# driver_board.net
KiCad netlist of a schematic drawn in EAGLE
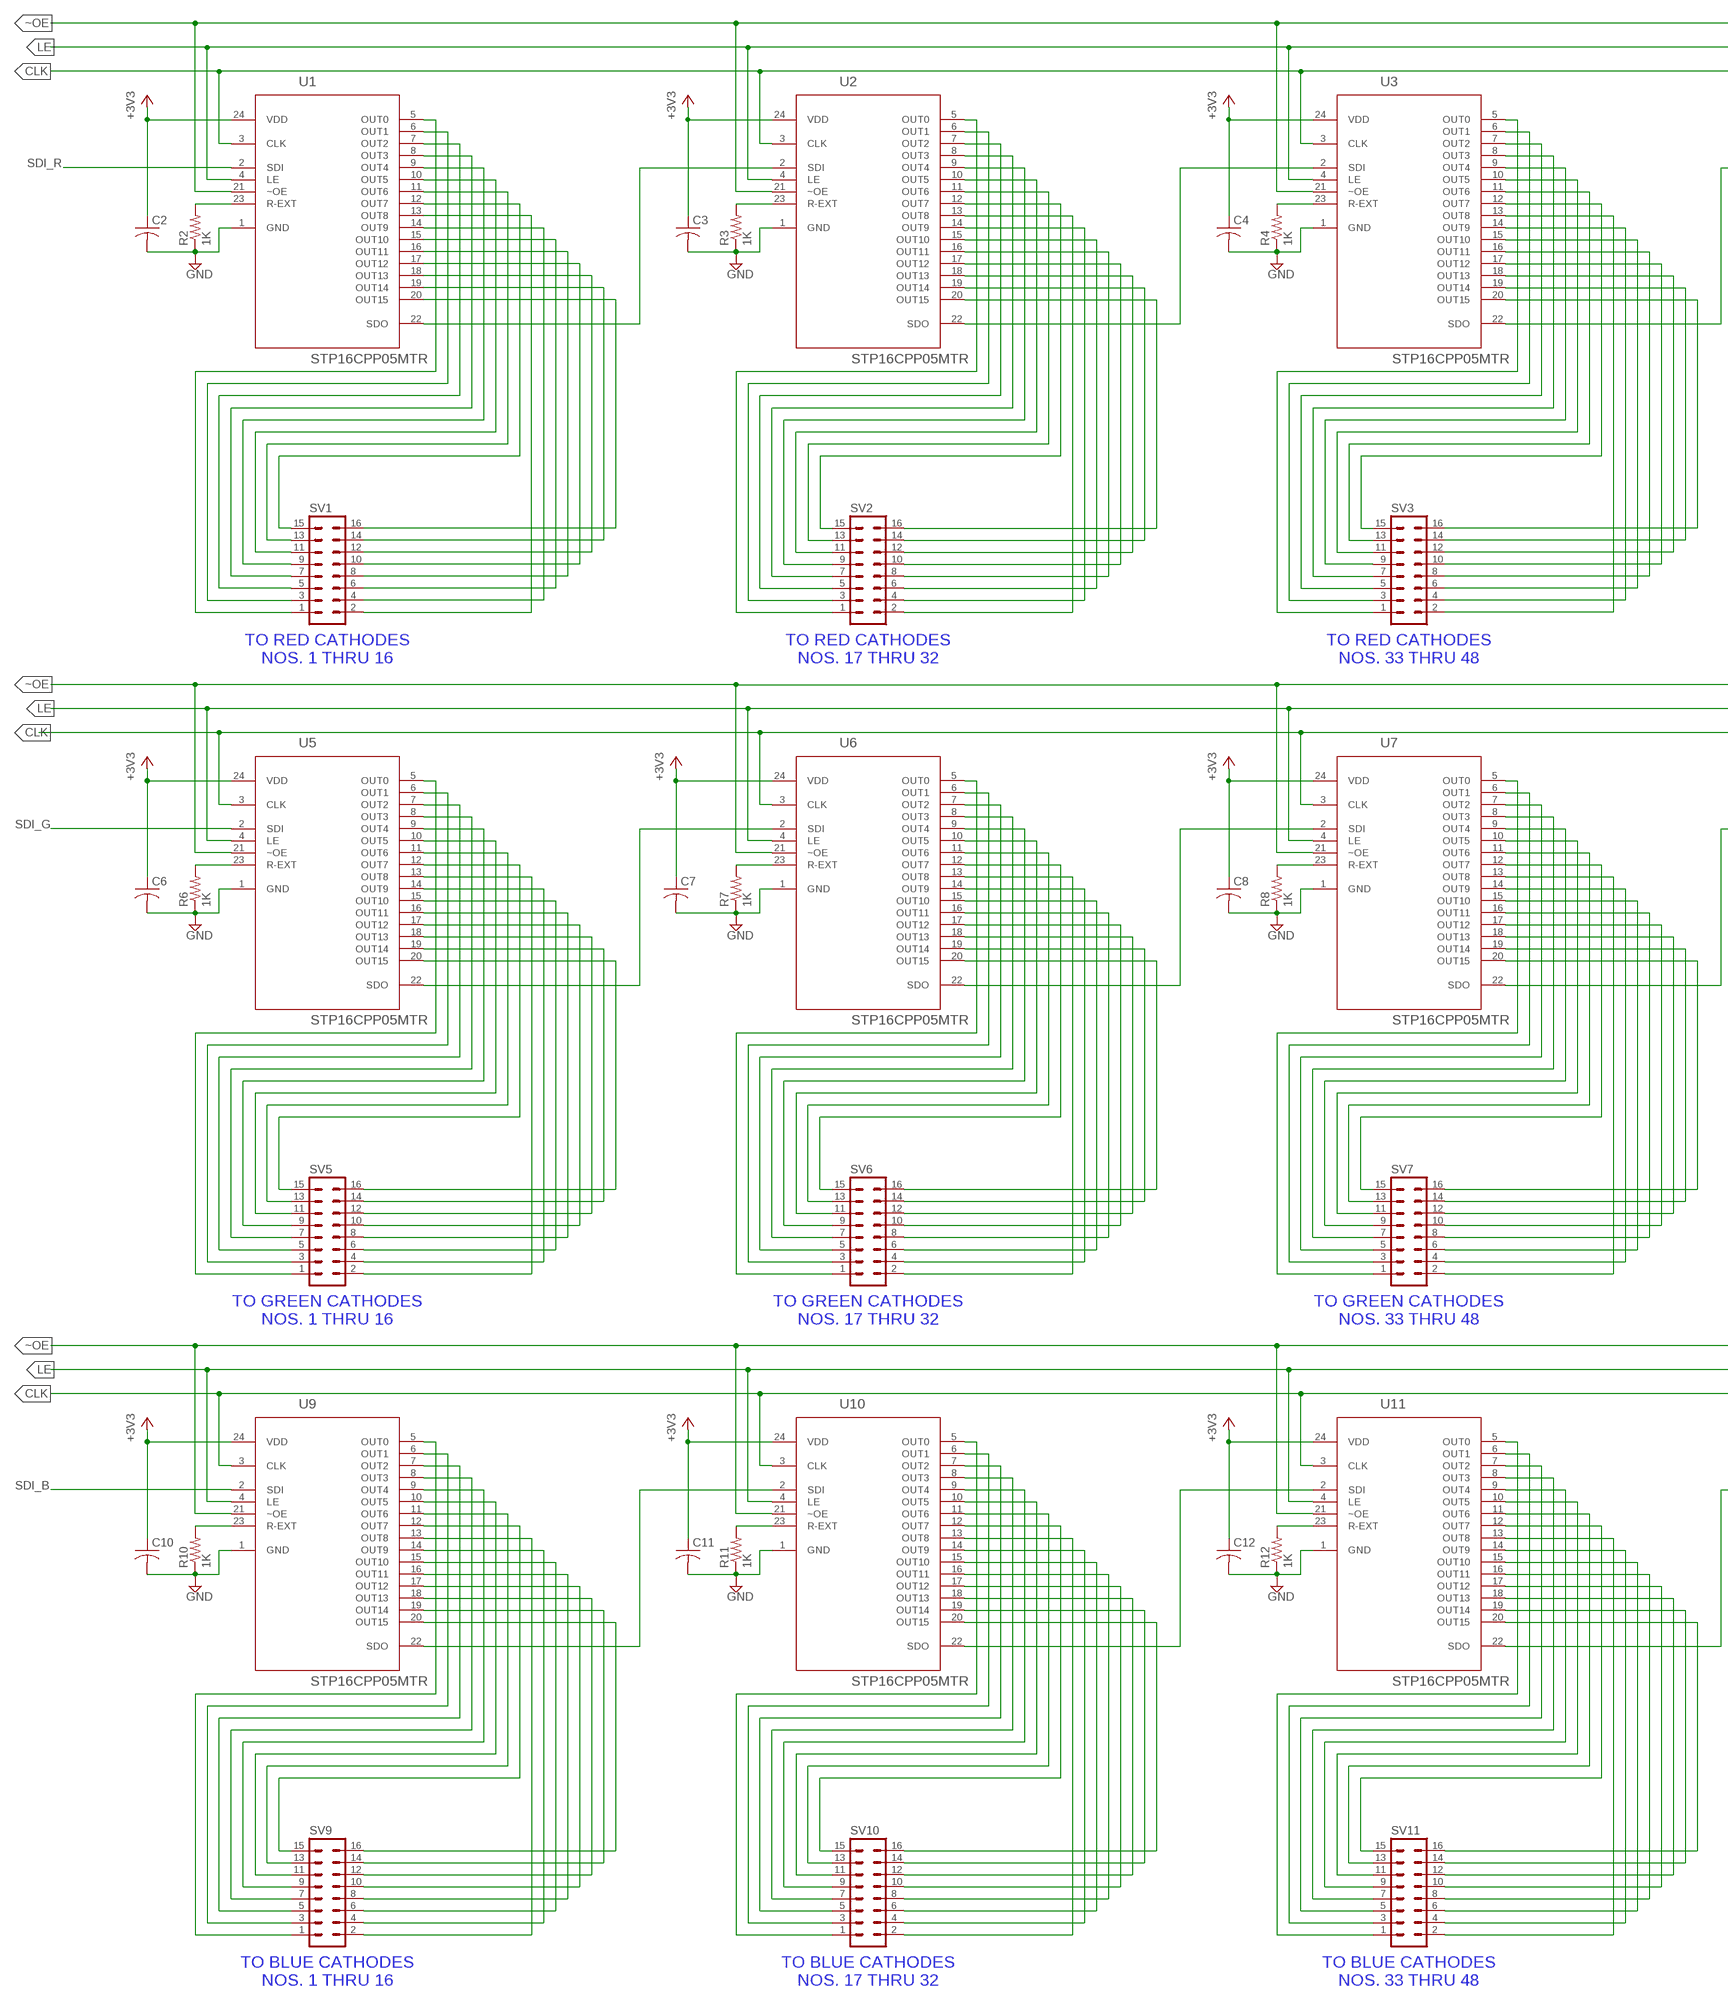
[diagram p0: schematic, sheet 1, part 1 of 2]
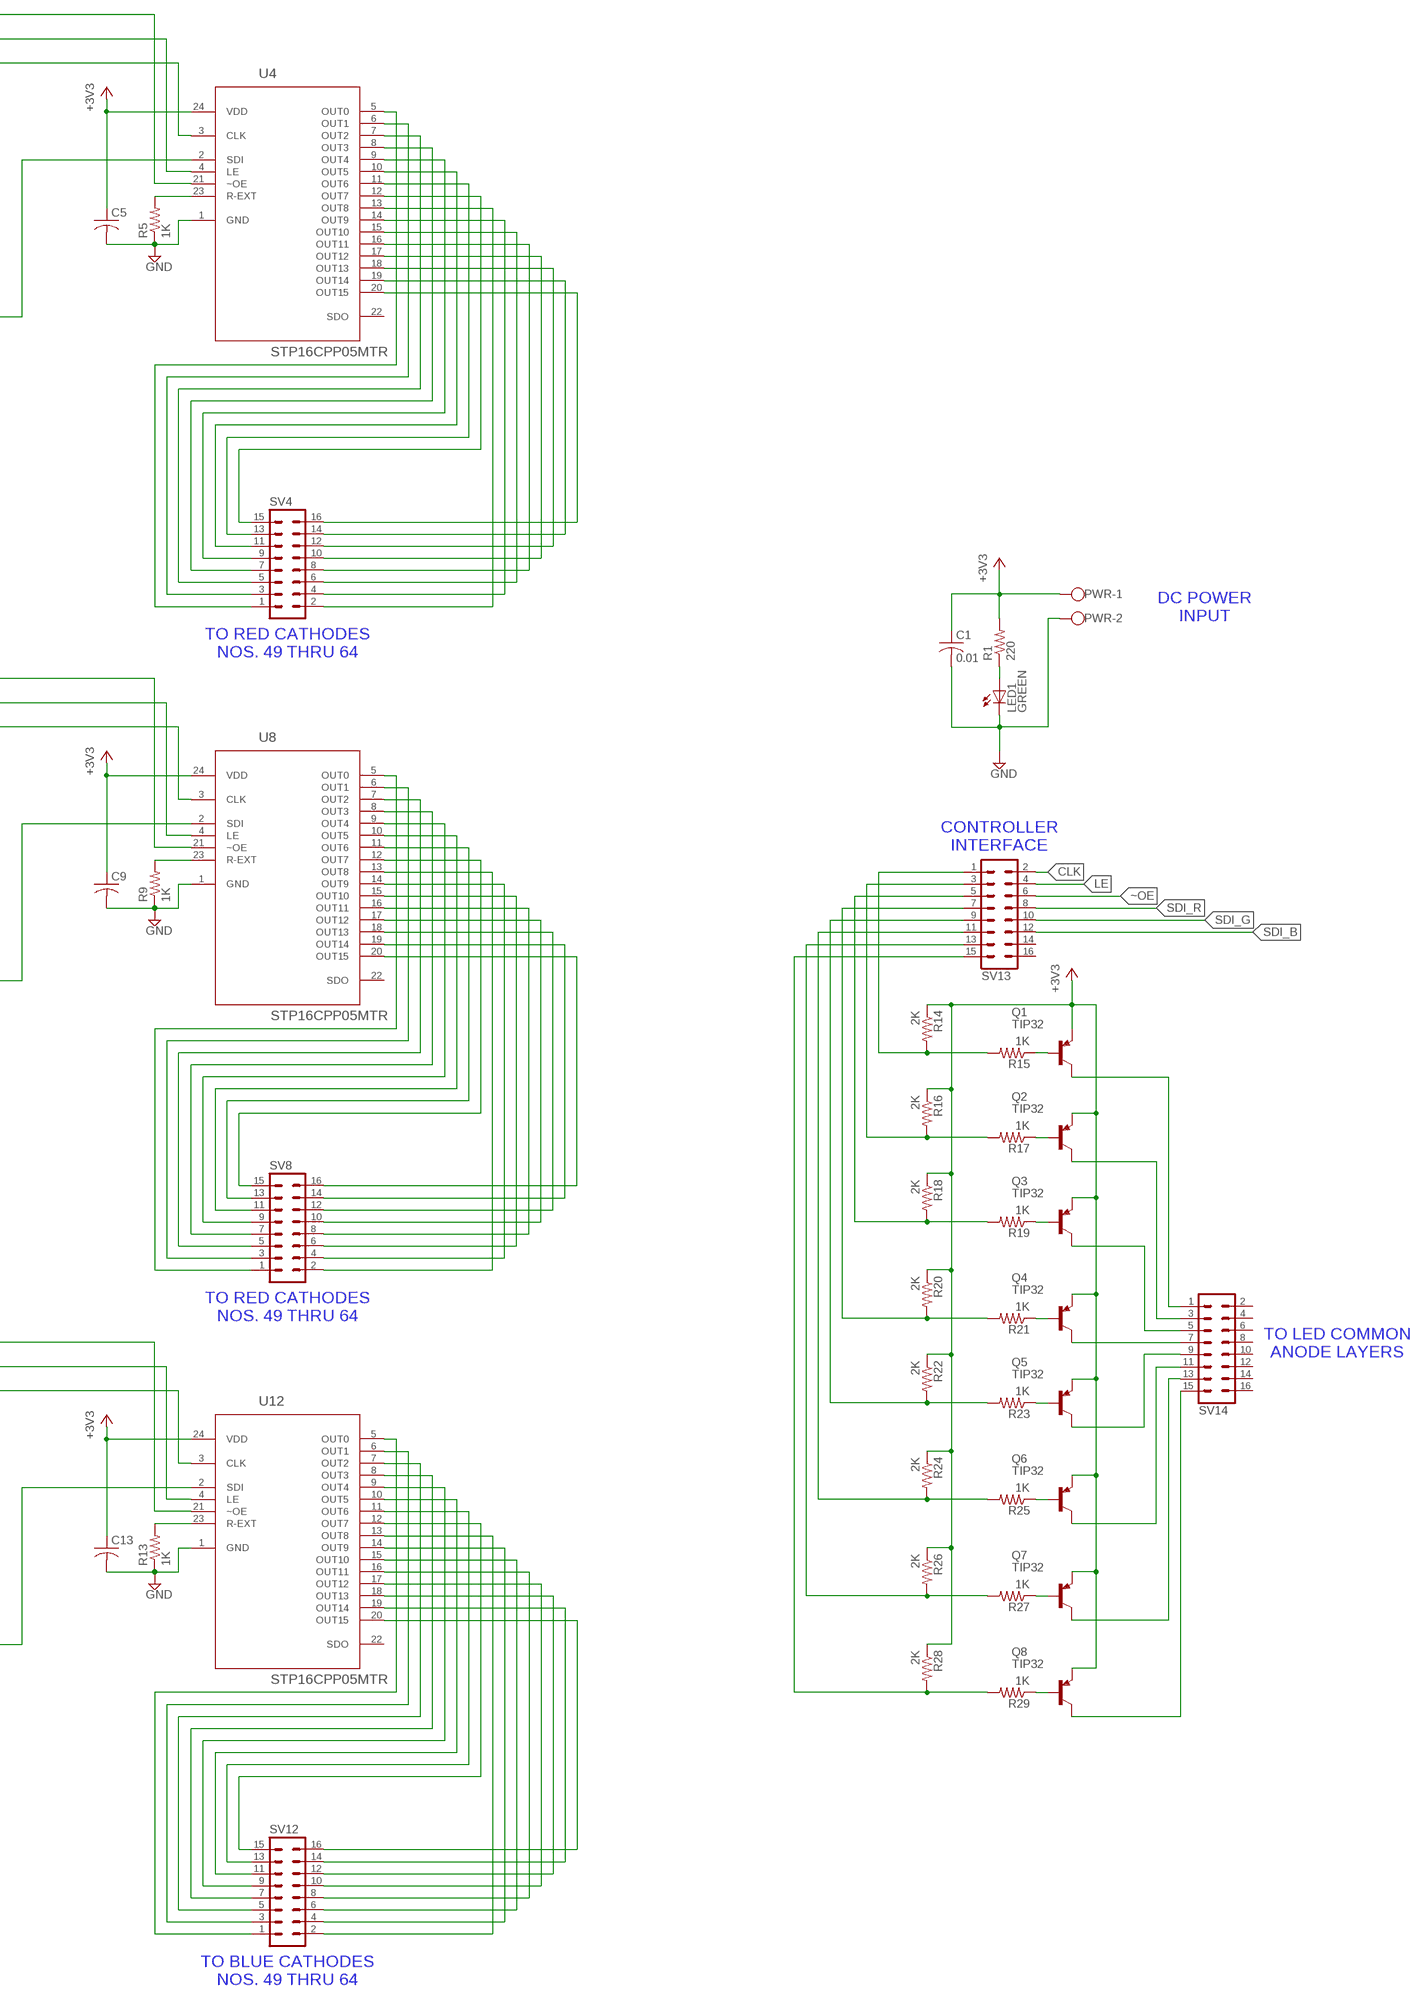
[diagram p1: schematic, sheet 1, part 2 of 2]

(export (version "E")
  (design (tool "Eeschema 10.0.6"))
  (components
    (comp (ref "C1")
      (value "0.01")
      (footprint "eagle-import:C0805")
      (fields (field (name "MPN") "MCCA001261"))
      (libsource (lib "eagle-import") (part "C-USC0805"))
    )
    (comp (ref "C2")
      (value "C-USC0805")
      (footprint "eagle-import:C0805")
      (fields (field (name "MPN") "MCCA001261"))
      (libsource (lib "eagle-import") (part "C-USC0805"))
    )
    (comp (ref "C3")
      (value "C-USC0805")
      (footprint "eagle-import:C0805")
      (fields (field (name "MPN") "MCCA001261"))
      (libsource (lib "eagle-import") (part "C-USC0805"))
    )
    (comp (ref "C4")
      (value "C-USC0805")
      (footprint "eagle-import:C0805")
      (fields (field (name "MPN") "MCCA001261"))
      (libsource (lib "eagle-import") (part "C-USC0805"))
    )
    (comp (ref "C5")
      (value "C-USC0805")
      (footprint "eagle-import:C0805")
      (fields (field (name "MPN") "MCCA001261"))
      (libsource (lib "eagle-import") (part "C-USC0805"))
    )
    (comp (ref "C6")
      (value "C-USC0805")
      (footprint "eagle-import:C0805")
      (fields (field (name "MPN") "MCCA001261"))
      (libsource (lib "eagle-import") (part "C-USC0805"))
    )
    (comp (ref "C7")
      (value "C-USC0805")
      (footprint "eagle-import:C0805")
      (fields (field (name "MPN") "MCCA001261"))
      (libsource (lib "eagle-import") (part "C-USC0805"))
    )
    (comp (ref "C8")
      (value "C-USC0805")
      (footprint "eagle-import:C0805")
      (fields (field (name "MPN") "MCCA001261"))
      (libsource (lib "eagle-import") (part "C-USC0805"))
    )
    (comp (ref "C9")
      (value "C-USC0805")
      (footprint "eagle-import:C0805")
      (fields (field (name "MPN") "MCCA001261"))
      (libsource (lib "eagle-import") (part "C-USC0805"))
    )
    (comp (ref "C10")
      (value "C-USC0805")
      (footprint "eagle-import:C0805")
      (fields (field (name "MPN") "MCCA001261"))
      (libsource (lib "eagle-import") (part "C-USC0805"))
    )
    (comp (ref "C11")
      (value "C-USC0805")
      (footprint "eagle-import:C0805")
      (fields (field (name "MPN") "MCCA001261"))
      (libsource (lib "eagle-import") (part "C-USC0805"))
    )
    (comp (ref "C12")
      (value "C-USC0805")
      (footprint "eagle-import:C0805")
      (fields (field (name "MPN") "MCCA001261"))
      (libsource (lib "eagle-import") (part "C-USC0805"))
    )
    (comp (ref "C13")
      (value "C-USC0805")
      (footprint "eagle-import:C0805")
      (fields (field (name "MPN") "MCCA001261"))
      (libsource (lib "eagle-import") (part "C-USC0805"))
    )
    (comp (ref "LED1")
      (value "GREEN")
      (footprint "eagle-import:LED5MM")
      (fields (field (name "MF") "SLI (CML/IDI)") (field (name "MPN") "CMD17-21VGD/TR8"))
      (libsource (lib "eagle-import") (part "LED5MM"))
    )
    (comp (ref "PWR")
      (value "W237-102")
      (footprint "eagle-import:W237-102")
      (fields (field (name "MPN") "237-102") (field (name "OC_NEWARK") "unknown"))
      (libsource (lib "eagle-import") (part "W237-102"))
    )
    (comp (ref "Q1")
      (value "TIP32")
      (footprint "eagle-import:TO220AV")
      (fields (field (name "MF") "ON SEMICONDUCTOR") (field (name "MPN") "TIP32BG"))
      (libsource (lib "eagle-import") (part "TIP32"))
    )
    (comp (ref "Q2")
      (value "TIP32")
      (footprint "eagle-import:TO220AV")
      (fields (field (name "MF") "ON SEMICONDUCTOR") (field (name "MPN") "TIP32BG"))
      (libsource (lib "eagle-import") (part "TIP32"))
    )
    (comp (ref "Q3")
      (value "TIP32")
      (footprint "eagle-import:TO220AV")
      (fields (field (name "MF") "ON SEMICONDUCTOR") (field (name "MPN") "TIP32BG"))
      (libsource (lib "eagle-import") (part "TIP32"))
    )
    (comp (ref "Q4")
      (value "TIP32")
      (footprint "eagle-import:TO220AV")
      (fields (field (name "MF") "ON SEMICONDUCTOR") (field (name "MPN") "TIP32BG"))
      (libsource (lib "eagle-import") (part "TIP32"))
    )
    (comp (ref "Q5")
      (value "TIP32")
      (footprint "eagle-import:TO220AV")
      (fields (field (name "MF") "ON SEMICONDUCTOR") (field (name "MPN") "TIP32BG"))
      (libsource (lib "eagle-import") (part "TIP32"))
    )
    (comp (ref "Q6")
      (value "TIP32")
      (footprint "eagle-import:TO220AV")
      (fields (field (name "MF") "ON SEMICONDUCTOR") (field (name "MPN") "TIP32BG"))
      (libsource (lib "eagle-import") (part "TIP32"))
    )
    (comp (ref "Q7")
      (value "TIP32")
      (footprint "eagle-import:TO220AV")
      (fields (field (name "MF") "ON SEMICONDUCTOR") (field (name "MPN") "TIP32BG"))
      (libsource (lib "eagle-import") (part "TIP32"))
    )
    (comp (ref "Q8")
      (value "TIP32")
      (footprint "eagle-import:TO220AV")
      (fields (field (name "MF") "ON SEMICONDUCTOR") (field (name "MPN") "TIP32BG"))
      (libsource (lib "eagle-import") (part "TIP32"))
    )
    (comp (ref "R1")
      (value "220")
      (footprint "eagle-import:R0805")
      (fields (field (name "MPN") "MCHP05W4F2200T5E"))
      (libsource (lib "eagle-import") (part "R-US_R0805"))
    )
    (comp (ref "R2")
      (value "1K")
      (footprint "eagle-import:R0805")
      (fields (field (name "MPN") "MC01W080511K"))
      (libsource (lib "eagle-import") (part "R-US_R0805"))
    )
    (comp (ref "R3")
      (value "1K")
      (footprint "eagle-import:R0805")
      (fields (field (name "MPN") "MC01W080511K"))
      (libsource (lib "eagle-import") (part "R-US_R0805"))
    )
    (comp (ref "R4")
      (value "1K")
      (footprint "eagle-import:R0805")
      (fields (field (name "MPN") "MC01W080511K"))
      (libsource (lib "eagle-import") (part "R-US_R0805"))
    )
    (comp (ref "R5")
      (value "1K")
      (footprint "eagle-import:R0805")
      (fields (field (name "MPN") "MC01W080511K"))
      (libsource (lib "eagle-import") (part "R-US_R0805"))
    )
    (comp (ref "R6")
      (value "1K")
      (footprint "eagle-import:R0805")
      (fields (field (name "MPN") "MC01W080511K"))
      (libsource (lib "eagle-import") (part "R-US_R0805"))
    )
    (comp (ref "R7")
      (value "1K")
      (footprint "eagle-import:R0805")
      (fields (field (name "MPN") "MC01W080511K"))
      (libsource (lib "eagle-import") (part "R-US_R0805"))
    )
    (comp (ref "R8")
      (value "1K")
      (footprint "eagle-import:R0805")
      (fields (field (name "MPN") "MC01W080511K"))
      (libsource (lib "eagle-import") (part "R-US_R0805"))
    )
    (comp (ref "R9")
      (value "1K")
      (footprint "eagle-import:R0805")
      (fields (field (name "MPN") "MC01W080511K"))
      (libsource (lib "eagle-import") (part "R-US_R0805"))
    )
    (comp (ref "R10")
      (value "1K")
      (footprint "eagle-import:R0805")
      (fields (field (name "MPN") "MC01W080511K"))
      (libsource (lib "eagle-import") (part "R-US_R0805"))
    )
    (comp (ref "R11")
      (value "1K")
      (footprint "eagle-import:R0805")
      (fields (field (name "MPN") "MC01W080511K"))
      (libsource (lib "eagle-import") (part "R-US_R0805"))
    )
    (comp (ref "R12")
      (value "1K")
      (footprint "eagle-import:R0805")
      (fields (field (name "MPN") "MC01W080511K"))
      (libsource (lib "eagle-import") (part "R-US_R0805"))
    )
    (comp (ref "R13")
      (value "1K")
      (footprint "eagle-import:R0805")
      (fields (field (name "MPN") "MC01W080511K"))
      (libsource (lib "eagle-import") (part "R-US_R0805"))
    )
    (comp (ref "R14")
      (value "2K")
      (footprint "eagle-import:R0805")
      (libsource (lib "eagle-import") (part "R-US_R0805"))
    )
    (comp (ref "R15")
      (value "1K")
      (footprint "eagle-import:R0805")
      (libsource (lib "eagle-import") (part "R-US_R0805"))
    )
    (comp (ref "R16")
      (value "2K")
      (footprint "eagle-import:R0805")
      (libsource (lib "eagle-import") (part "R-US_R0805"))
    )
    (comp (ref "R17")
      (value "1K")
      (footprint "eagle-import:R0805")
      (libsource (lib "eagle-import") (part "R-US_R0805"))
    )
    (comp (ref "R18")
      (value "2K")
      (footprint "eagle-import:R0805")
      (libsource (lib "eagle-import") (part "R-US_R0805"))
    )
    (comp (ref "R19")
      (value "1K")
      (footprint "eagle-import:R0805")
      (libsource (lib "eagle-import") (part "R-US_R0805"))
    )
    (comp (ref "R20")
      (value "2K")
      (footprint "eagle-import:R0805")
      (libsource (lib "eagle-import") (part "R-US_R0805"))
    )
    (comp (ref "R21")
      (value "1K")
      (footprint "eagle-import:R0805")
      (libsource (lib "eagle-import") (part "R-US_R0805"))
    )
    (comp (ref "R22")
      (value "2K")
      (footprint "eagle-import:R0805")
      (libsource (lib "eagle-import") (part "R-US_R0805"))
    )
    (comp (ref "R23")
      (value "1K")
      (footprint "eagle-import:R0805")
      (libsource (lib "eagle-import") (part "R-US_R0805"))
    )
    (comp (ref "R24")
      (value "2K")
      (footprint "eagle-import:R0805")
      (libsource (lib "eagle-import") (part "R-US_R0805"))
    )
    (comp (ref "R25")
      (value "1K")
      (footprint "eagle-import:R0805")
      (libsource (lib "eagle-import") (part "R-US_R0805"))
    )
    (comp (ref "R26")
      (value "2K")
      (footprint "eagle-import:R0805")
      (libsource (lib "eagle-import") (part "R-US_R0805"))
    )
    (comp (ref "R27")
      (value "1K")
      (footprint "eagle-import:R0805")
      (libsource (lib "eagle-import") (part "R-US_R0805"))
    )
    (comp (ref "R28")
      (value "2K")
      (footprint "eagle-import:R0805")
      (libsource (lib "eagle-import") (part "R-US_R0805"))
    )
    (comp (ref "R29")
      (value "1K")
      (footprint "eagle-import:R0805")
      (libsource (lib "eagle-import") (part "R-US_R0805"))
    )
    (comp (ref "SV1")
      (value "16PL")
      (footprint "eagle-import:16PL")
      (fields (field (name "MF") "FARNELL") (field (name "MPN") "008380016000010"))
      (libsource (lib "eagle-import") (part "16PL"))
    )
    (comp (ref "SV2")
      (value "16PL")
      (footprint "eagle-import:16PL")
      (fields (field (name "MF") "FARNELL") (field (name "MPN") "008380016000010"))
      (libsource (lib "eagle-import") (part "16PL"))
    )
    (comp (ref "SV3")
      (value "16PL")
      (footprint "eagle-import:16PL")
      (fields (field (name "MF") "FARNELL") (field (name "MPN") "008380016000010"))
      (libsource (lib "eagle-import") (part "16PL"))
    )
    (comp (ref "SV4")
      (value "16PL")
      (footprint "eagle-import:16PL")
      (fields (field (name "MF") "FARNELL") (field (name "MPN") "008380016000010"))
      (libsource (lib "eagle-import") (part "16PL"))
    )
    (comp (ref "SV5")
      (value "16PL")
      (footprint "eagle-import:16PL")
      (fields (field (name "MF") "FARNELL") (field (name "MPN") "008380016000010"))
      (libsource (lib "eagle-import") (part "16PL"))
    )
    (comp (ref "SV6")
      (value "16PL")
      (footprint "eagle-import:16PL")
      (fields (field (name "MF") "FARNELL") (field (name "MPN") "008380016000010"))
      (libsource (lib "eagle-import") (part "16PL"))
    )
    (comp (ref "SV7")
      (value "16PL")
      (footprint "eagle-import:16PL")
      (fields (field (name "MF") "FARNELL") (field (name "MPN") "008380016000010"))
      (libsource (lib "eagle-import") (part "16PL"))
    )
    (comp (ref "SV8")
      (value "16PL")
      (footprint "eagle-import:16PL")
      (fields (field (name "MF") "FARNELL") (field (name "MPN") "008380016000010"))
      (libsource (lib "eagle-import") (part "16PL"))
    )
    (comp (ref "SV9")
      (value "16PL")
      (footprint "eagle-import:16PL")
      (fields (field (name "MF") "FARNELL") (field (name "MPN") "008380016000010"))
      (libsource (lib "eagle-import") (part "16PL"))
    )
    (comp (ref "SV10")
      (value "16PL")
      (footprint "eagle-import:16PL")
      (fields (field (name "MF") "FARNELL") (field (name "MPN") "008380016000010"))
      (libsource (lib "eagle-import") (part "16PL"))
    )
    (comp (ref "SV11")
      (value "16PL")
      (footprint "eagle-import:16PL")
      (fields (field (name "MF") "FARNELL") (field (name "MPN") "008380016000010"))
      (libsource (lib "eagle-import") (part "16PL"))
    )
    (comp (ref "SV12")
      (value "16PL")
      (footprint "eagle-import:16PL")
      (fields (field (name "MF") "FARNELL") (field (name "MPN") "008380016000010"))
      (libsource (lib "eagle-import") (part "16PL"))
    )
    (comp (ref "SV13")
      (value "16PL")
      (footprint "eagle-import:16PL")
      (fields (field (name "MF") "FARNELL") (field (name "MPN") "008380016000010"))
      (libsource (lib "eagle-import") (part "16PL"))
    )
    (comp (ref "SV14")
      (value "16PL")
      (footprint "eagle-import:16PL")
      (fields (field (name "MF") "FARNELL") (field (name "MPN") "008380016000010"))
      (libsource (lib "eagle-import") (part "16PL"))
    )
    (comp (ref "U1")
      (value "STP16CPP05MTR")
      (footprint "eagle-import:SOIC127P1032X265-24N")
      (libsource (lib "eagle-import") (part "STP16CPP05MTR"))
    )
    (comp (ref "U2")
      (value "STP16CPP05MTR")
      (footprint "eagle-import:SOIC127P1032X265-24N")
      (libsource (lib "eagle-import") (part "STP16CPP05MTR"))
    )
    (comp (ref "U3")
      (value "STP16CPP05MTR")
      (footprint "eagle-import:SOIC127P1032X265-24N")
      (libsource (lib "eagle-import") (part "STP16CPP05MTR"))
    )
    (comp (ref "U4")
      (value "STP16CPP05MTR")
      (footprint "eagle-import:SOIC127P1032X265-24N")
      (libsource (lib "eagle-import") (part "STP16CPP05MTR"))
    )
    (comp (ref "U5")
      (value "STP16CPP05MTR")
      (footprint "eagle-import:SOIC127P1032X265-24N")
      (libsource (lib "eagle-import") (part "STP16CPP05MTR"))
    )
    (comp (ref "U6")
      (value "STP16CPP05MTR")
      (footprint "eagle-import:SOIC127P1032X265-24N")
      (libsource (lib "eagle-import") (part "STP16CPP05MTR"))
    )
    (comp (ref "U7")
      (value "STP16CPP05MTR")
      (footprint "eagle-import:SOIC127P1032X265-24N")
      (libsource (lib "eagle-import") (part "STP16CPP05MTR"))
    )
    (comp (ref "U8")
      (value "STP16CPP05MTR")
      (footprint "eagle-import:SOIC127P1032X265-24N")
      (libsource (lib "eagle-import") (part "STP16CPP05MTR"))
    )
    (comp (ref "U9")
      (value "STP16CPP05MTR")
      (footprint "eagle-import:SOIC127P1032X265-24N")
      (libsource (lib "eagle-import") (part "STP16CPP05MTR"))
    )
    (comp (ref "U10")
      (value "STP16CPP05MTR")
      (footprint "eagle-import:SOIC127P1032X265-24N")
      (libsource (lib "eagle-import") (part "STP16CPP05MTR"))
    )
    (comp (ref "U11")
      (value "STP16CPP05MTR")
      (footprint "eagle-import:SOIC127P1032X265-24N")
      (libsource (lib "eagle-import") (part "STP16CPP05MTR"))
    )
    (comp (ref "U12")
      (value "STP16CPP05MTR")
      (footprint "eagle-import:SOIC127P1032X265-24N")
      (libsource (lib "eagle-import") (part "STP16CPP05MTR"))
    )
  )
  (nets
    (net (code "1") (name "+3V3") (class "Default")
      (node (ref "C1") (pin "1") (pinfunction "1_1") (pintype "passive"))
      (node (ref "C10") (pin "1") (pinfunction "1_1") (pintype "passive"))
      (node (ref "C11") (pin "1") (pinfunction "1_1") (pintype "passive"))
      (node (ref "C12") (pin "1") (pinfunction "1_1") (pintype "passive"))
      (node (ref "C13") (pin "1") (pinfunction "1_1") (pintype "passive"))
      (node (ref "C2") (pin "1") (pinfunction "1_1") (pintype "passive"))
      (node (ref "C3") (pin "1") (pinfunction "1_1") (pintype "passive"))
      (node (ref "C4") (pin "1") (pinfunction "1_1") (pintype "passive"))
      (node (ref "C5") (pin "1") (pinfunction "1_1") (pintype "passive"))
      (node (ref "C6") (pin "1") (pinfunction "1_1") (pintype "passive"))
      (node (ref "C7") (pin "1") (pinfunction "1_1") (pintype "passive"))
      (node (ref "C8") (pin "1") (pinfunction "1_1") (pintype "passive"))
      (node (ref "C9") (pin "1") (pinfunction "1_1") (pintype "passive"))
      (node (ref "PWR") (pin "1") (pinfunction "KL_1") (pintype "passive"))
      (node (ref "Q1") (pin "E") (pinfunction "E_E") (pintype "passive"))
      (node (ref "Q2") (pin "E") (pinfunction "E_E") (pintype "passive"))
      (node (ref "Q3") (pin "E") (pinfunction "E_E") (pintype "passive"))
      (node (ref "Q4") (pin "E") (pinfunction "E_E") (pintype "passive"))
      (node (ref "Q5") (pin "E") (pinfunction "E_E") (pintype "passive"))
      (node (ref "Q6") (pin "E") (pinfunction "E_E") (pintype "passive"))
      (node (ref "Q7") (pin "E") (pinfunction "E_E") (pintype "passive"))
      (node (ref "Q8") (pin "E") (pinfunction "E_E") (pintype "passive"))
      (node (ref "R1") (pin "2") (pinfunction "2_2") (pintype "passive"))
      (node (ref "R14") (pin "1") (pinfunction "1_1") (pintype "passive"))
      (node (ref "R16") (pin "1") (pinfunction "1_1") (pintype "passive"))
      (node (ref "R18") (pin "1") (pinfunction "1_1") (pintype "passive"))
      (node (ref "R20") (pin "1") (pinfunction "1_1") (pintype "passive"))
      (node (ref "R22") (pin "1") (pinfunction "1_1") (pintype "passive"))
      (node (ref "R24") (pin "1") (pinfunction "1_1") (pintype "passive"))
      (node (ref "R26") (pin "1") (pinfunction "1_1") (pintype "passive"))
      (node (ref "R28") (pin "1") (pinfunction "1_1") (pintype "passive"))
      (node (ref "U1") (pin "24") (pinfunction "VDD_24") (pintype "power_in"))
      (node (ref "U10") (pin "24") (pinfunction "VDD_24") (pintype "power_in"))
      (node (ref "U11") (pin "24") (pinfunction "VDD_24") (pintype "power_in"))
      (node (ref "U12") (pin "24") (pinfunction "VDD_24") (pintype "power_in"))
      (node (ref "U2") (pin "24") (pinfunction "VDD_24") (pintype "power_in"))
      (node (ref "U3") (pin "24") (pinfunction "VDD_24") (pintype "power_in"))
      (node (ref "U4") (pin "24") (pinfunction "VDD_24") (pintype "power_in"))
      (node (ref "U5") (pin "24") (pinfunction "VDD_24") (pintype "power_in"))
      (node (ref "U6") (pin "24") (pinfunction "VDD_24") (pintype "power_in"))
      (node (ref "U7") (pin "24") (pinfunction "VDD_24") (pintype "power_in"))
      (node (ref "U8") (pin "24") (pinfunction "VDD_24") (pintype "power_in"))
      (node (ref "U9") (pin "24") (pinfunction "VDD_24") (pintype "power_in"))
    )
    (net (code "2") (name "/~{OE}") (class "Default")
      (node (ref "SV13") (pin "6") (pinfunction "6_6") (pintype "passive"))
      (node (ref "U1") (pin "21") (pinfunction "~{OE}_21") (pintype "input"))
      (node (ref "U10") (pin "21") (pinfunction "~{OE}_21") (pintype "input"))
      (node (ref "U11") (pin "21") (pinfunction "~{OE}_21") (pintype "input"))
      (node (ref "U12") (pin "21") (pinfunction "~{OE}_21") (pintype "input"))
      (node (ref "U2") (pin "21") (pinfunction "~{OE}_21") (pintype "input"))
      (node (ref "U3") (pin "21") (pinfunction "~{OE}_21") (pintype "input"))
      (node (ref "U4") (pin "21") (pinfunction "~{OE}_21") (pintype "input"))
      (node (ref "U5") (pin "21") (pinfunction "~{OE}_21") (pintype "input"))
      (node (ref "U6") (pin "21") (pinfunction "~{OE}_21") (pintype "input"))
      (node (ref "U7") (pin "21") (pinfunction "~{OE}_21") (pintype "input"))
      (node (ref "U8") (pin "21") (pinfunction "~{OE}_21") (pintype "input"))
      (node (ref "U9") (pin "21") (pinfunction "~{OE}_21") (pintype "input"))
    )
    (net (code "3") (name "CLK") (class "Default")
      (node (ref "SV13") (pin "2") (pinfunction "2_2") (pintype "passive"))
      (node (ref "U1") (pin "3") (pinfunction "CLK_3") (pintype "input"))
      (node (ref "U10") (pin "3") (pinfunction "CLK_3") (pintype "input"))
      (node (ref "U11") (pin "3") (pinfunction "CLK_3") (pintype "input"))
      (node (ref "U12") (pin "3") (pinfunction "CLK_3") (pintype "input"))
      (node (ref "U2") (pin "3") (pinfunction "CLK_3") (pintype "input"))
      (node (ref "U3") (pin "3") (pinfunction "CLK_3") (pintype "input"))
      (node (ref "U4") (pin "3") (pinfunction "CLK_3") (pintype "input"))
      (node (ref "U5") (pin "3") (pinfunction "CLK_3") (pintype "input"))
      (node (ref "U6") (pin "3") (pinfunction "CLK_3") (pintype "input"))
      (node (ref "U7") (pin "3") (pinfunction "CLK_3") (pintype "input"))
      (node (ref "U8") (pin "3") (pinfunction "CLK_3") (pintype "input"))
      (node (ref "U9") (pin "3") (pinfunction "CLK_3") (pintype "input"))
    )
    (net (code "4") (name "GND") (class "Default")
      (node (ref "C1") (pin "2") (pinfunction "2_2") (pintype "passive"))
      (node (ref "C10") (pin "2") (pinfunction "2_2") (pintype "passive"))
      (node (ref "C11") (pin "2") (pinfunction "2_2") (pintype "passive"))
      (node (ref "C12") (pin "2") (pinfunction "2_2") (pintype "passive"))
      (node (ref "C13") (pin "2") (pinfunction "2_2") (pintype "passive"))
      (node (ref "C2") (pin "2") (pinfunction "2_2") (pintype "passive"))
      (node (ref "C3") (pin "2") (pinfunction "2_2") (pintype "passive"))
      (node (ref "C4") (pin "2") (pinfunction "2_2") (pintype "passive"))
      (node (ref "C5") (pin "2") (pinfunction "2_2") (pintype "passive"))
      (node (ref "C6") (pin "2") (pinfunction "2_2") (pintype "passive"))
      (node (ref "C7") (pin "2") (pinfunction "2_2") (pintype "passive"))
      (node (ref "C8") (pin "2") (pinfunction "2_2") (pintype "passive"))
      (node (ref "C9") (pin "2") (pinfunction "2_2") (pintype "passive"))
      (node (ref "LED1") (pin "K") (pinfunction "C_K") (pintype "passive"))
      (node (ref "PWR") (pin "2") (pinfunction "KL_2") (pintype "passive"))
      (node (ref "R10") (pin "1") (pinfunction "1_1") (pintype "passive"))
      (node (ref "R11") (pin "1") (pinfunction "1_1") (pintype "passive"))
      (node (ref "R12") (pin "1") (pinfunction "1_1") (pintype "passive"))
      (node (ref "R13") (pin "1") (pinfunction "1_1") (pintype "passive"))
      (node (ref "R2") (pin "1") (pinfunction "1_1") (pintype "passive"))
      (node (ref "R3") (pin "1") (pinfunction "1_1") (pintype "passive"))
      (node (ref "R4") (pin "1") (pinfunction "1_1") (pintype "passive"))
      (node (ref "R5") (pin "1") (pinfunction "1_1") (pintype "passive"))
      (node (ref "R6") (pin "1") (pinfunction "1_1") (pintype "passive"))
      (node (ref "R7") (pin "1") (pinfunction "1_1") (pintype "passive"))
      (node (ref "R8") (pin "1") (pinfunction "1_1") (pintype "passive"))
      (node (ref "R9") (pin "1") (pinfunction "1_1") (pintype "passive"))
      (node (ref "U1") (pin "1") (pinfunction "GND_1") (pintype "passive"))
      (node (ref "U10") (pin "1") (pinfunction "GND_1") (pintype "passive"))
      (node (ref "U11") (pin "1") (pinfunction "GND_1") (pintype "passive"))
      (node (ref "U12") (pin "1") (pinfunction "GND_1") (pintype "passive"))
      (node (ref "U2") (pin "1") (pinfunction "GND_1") (pintype "passive"))
      (node (ref "U3") (pin "1") (pinfunction "GND_1") (pintype "passive"))
      (node (ref "U4") (pin "1") (pinfunction "GND_1") (pintype "passive"))
      (node (ref "U5") (pin "1") (pinfunction "GND_1") (pintype "passive"))
      (node (ref "U6") (pin "1") (pinfunction "GND_1") (pintype "passive"))
      (node (ref "U7") (pin "1") (pinfunction "GND_1") (pintype "passive"))
      (node (ref "U8") (pin "1") (pinfunction "GND_1") (pintype "passive"))
      (node (ref "U9") (pin "1") (pinfunction "GND_1") (pintype "passive"))
    )
    (net (code "5") (name "LE") (class "Default")
      (node (ref "SV13") (pin "4") (pinfunction "4_4") (pintype "passive"))
      (node (ref "U1") (pin "4") (pinfunction "LE_4") (pintype "input"))
      (node (ref "U10") (pin "4") (pinfunction "LE_4") (pintype "input"))
      (node (ref "U11") (pin "4") (pinfunction "LE_4") (pintype "input"))
      (node (ref "U12") (pin "4") (pinfunction "LE_4") (pintype "input"))
      (node (ref "U2") (pin "4") (pinfunction "LE_4") (pintype "input"))
      (node (ref "U3") (pin "4") (pinfunction "LE_4") (pintype "input"))
      (node (ref "U4") (pin "4") (pinfunction "LE_4") (pintype "input"))
      (node (ref "U5") (pin "4") (pinfunction "LE_4") (pintype "input"))
      (node (ref "U6") (pin "4") (pinfunction "LE_4") (pintype "input"))
      (node (ref "U7") (pin "4") (pinfunction "LE_4") (pintype "input"))
      (node (ref "U8") (pin "4") (pinfunction "LE_4") (pintype "input"))
      (node (ref "U9") (pin "4") (pinfunction "LE_4") (pintype "input"))
    )
    (net (code "6") (name "Net-(LED1-PadA)") (class "Default")
      (node (ref "LED1") (pin "A") (pinfunction "A_A") (pintype "passive"))
      (node (ref "R1") (pin "1") (pinfunction "1_1") (pintype "passive"))
    )
    (net (code "7") (name "Net-(Q1-PadB)") (class "Default")
      (node (ref "Q1") (pin "B") (pinfunction "B_B") (pintype "passive"))
      (node (ref "R15") (pin "1") (pinfunction "1_1") (pintype "passive"))
    )
    (net (code "8") (name "Net-(Q1-PadC)") (class "Default")
      (node (ref "Q1") (pin "C") (pinfunction "C_C") (pintype "passive"))
      (node (ref "SV14") (pin "1") (pinfunction "1_1") (pintype "passive"))
    )
    (net (code "9") (name "Net-(Q2-PadB)") (class "Default")
      (node (ref "Q2") (pin "B") (pinfunction "B_B") (pintype "passive"))
      (node (ref "R17") (pin "1") (pinfunction "1_1") (pintype "passive"))
    )
    (net (code "10") (name "Net-(Q2-PadC)") (class "Default")
      (node (ref "Q2") (pin "C") (pinfunction "C_C") (pintype "passive"))
      (node (ref "SV14") (pin "3") (pinfunction "3_3") (pintype "passive"))
    )
    (net (code "11") (name "Net-(Q3-PadB)") (class "Default")
      (node (ref "Q3") (pin "B") (pinfunction "B_B") (pintype "passive"))
      (node (ref "R19") (pin "1") (pinfunction "1_1") (pintype "passive"))
    )
    (net (code "12") (name "Net-(Q3-PadC)") (class "Default")
      (node (ref "Q3") (pin "C") (pinfunction "C_C") (pintype "passive"))
      (node (ref "SV14") (pin "5") (pinfunction "5_5") (pintype "passive"))
    )
    (net (code "13") (name "Net-(Q4-PadB)") (class "Default")
      (node (ref "Q4") (pin "B") (pinfunction "B_B") (pintype "passive"))
      (node (ref "R21") (pin "1") (pinfunction "1_1") (pintype "passive"))
    )
    (net (code "14") (name "Net-(Q4-PadC)") (class "Default")
      (node (ref "Q4") (pin "C") (pinfunction "C_C") (pintype "passive"))
      (node (ref "SV14") (pin "7") (pinfunction "7_7") (pintype "passive"))
    )
    (net (code "15") (name "Net-(Q5-PadB)") (class "Default")
      (node (ref "Q5") (pin "B") (pinfunction "B_B") (pintype "passive"))
      (node (ref "R23") (pin "1") (pinfunction "1_1") (pintype "passive"))
    )
    (net (code "16") (name "Net-(Q5-PadC)") (class "Default")
      (node (ref "Q5") (pin "C") (pinfunction "C_C") (pintype "passive"))
      (node (ref "SV14") (pin "9") (pinfunction "9_9") (pintype "passive"))
    )
    (net (code "17") (name "Net-(Q6-PadB)") (class "Default")
      (node (ref "Q6") (pin "B") (pinfunction "B_B") (pintype "passive"))
      (node (ref "R25") (pin "1") (pinfunction "1_1") (pintype "passive"))
    )
    (net (code "18") (name "Net-(Q6-PadC)") (class "Default")
      (node (ref "Q6") (pin "C") (pinfunction "C_C") (pintype "passive"))
      (node (ref "SV14") (pin "11") (pinfunction "11_11") (pintype "passive"))
    )
    (net (code "19") (name "Net-(Q7-PadB)") (class "Default")
      (node (ref "Q7") (pin "B") (pinfunction "B_B") (pintype "passive"))
      (node (ref "R27") (pin "1") (pinfunction "1_1") (pintype "passive"))
    )
    (net (code "20") (name "Net-(Q7-PadC)") (class "Default")
      (node (ref "Q7") (pin "C") (pinfunction "C_C") (pintype "passive"))
      (node (ref "SV14") (pin "13") (pinfunction "13_13") (pintype "passive"))
    )
    (net (code "21") (name "Net-(Q8-PadB)") (class "Default")
      (node (ref "Q8") (pin "B") (pinfunction "B_B") (pintype "passive"))
      (node (ref "R29") (pin "1") (pinfunction "1_1") (pintype "passive"))
    )
    (net (code "22") (name "Net-(Q8-PadC)") (class "Default")
      (node (ref "Q8") (pin "C") (pinfunction "C_C") (pintype "passive"))
      (node (ref "SV14") (pin "15") (pinfunction "15_15") (pintype "passive"))
    )
    (net (code "23") (name "Net-(R14-Pad2)") (class "Default")
      (node (ref "R14") (pin "2") (pinfunction "2_2") (pintype "passive"))
      (node (ref "R15") (pin "2") (pinfunction "2_2") (pintype "passive"))
      (node (ref "SV13") (pin "1") (pinfunction "1_1") (pintype "passive"))
    )
    (net (code "24") (name "Net-(R16-Pad2)") (class "Default")
      (node (ref "R16") (pin "2") (pinfunction "2_2") (pintype "passive"))
      (node (ref "R17") (pin "2") (pinfunction "2_2") (pintype "passive"))
      (node (ref "SV13") (pin "3") (pinfunction "3_3") (pintype "passive"))
    )
    (net (code "25") (name "Net-(R18-Pad2)") (class "Default")
      (node (ref "R18") (pin "2") (pinfunction "2_2") (pintype "passive"))
      (node (ref "R19") (pin "2") (pinfunction "2_2") (pintype "passive"))
      (node (ref "SV13") (pin "5") (pinfunction "5_5") (pintype "passive"))
    )
    (net (code "26") (name "Net-(R20-Pad2)") (class "Default")
      (node (ref "R20") (pin "2") (pinfunction "2_2") (pintype "passive"))
      (node (ref "R21") (pin "2") (pinfunction "2_2") (pintype "passive"))
      (node (ref "SV13") (pin "7") (pinfunction "7_7") (pintype "passive"))
    )
    (net (code "27") (name "Net-(R22-Pad2)") (class "Default")
      (node (ref "R22") (pin "2") (pinfunction "2_2") (pintype "passive"))
      (node (ref "R23") (pin "2") (pinfunction "2_2") (pintype "passive"))
      (node (ref "SV13") (pin "9") (pinfunction "9_9") (pintype "passive"))
    )
    (net (code "28") (name "Net-(R24-Pad2)") (class "Default")
      (node (ref "R24") (pin "2") (pinfunction "2_2") (pintype "passive"))
      (node (ref "R25") (pin "2") (pinfunction "2_2") (pintype "passive"))
      (node (ref "SV13") (pin "11") (pinfunction "11_11") (pintype "passive"))
    )
    (net (code "29") (name "Net-(R26-Pad2)") (class "Default")
      (node (ref "R26") (pin "2") (pinfunction "2_2") (pintype "passive"))
      (node (ref "R27") (pin "2") (pinfunction "2_2") (pintype "passive"))
      (node (ref "SV13") (pin "13") (pinfunction "13_13") (pintype "passive"))
    )
    (net (code "30") (name "Net-(R28-Pad2)") (class "Default")
      (node (ref "R28") (pin "2") (pinfunction "2_2") (pintype "passive"))
      (node (ref "R29") (pin "2") (pinfunction "2_2") (pintype "passive"))
      (node (ref "SV13") (pin "15") (pinfunction "15_15") (pintype "passive"))
    )
    (net (code "31") (name "Net-(U1-OUT0)") (class "Default")
      (node (ref "SV1") (pin "1") (pinfunction "1_1") (pintype "passive"))
      (node (ref "U1") (pin "5") (pinfunction "OUT0_5") (pintype "output"))
    )
    (net (code "32") (name "Net-(U1-OUT1)") (class "Default")
      (node (ref "SV1") (pin "3") (pinfunction "3_3") (pintype "passive"))
      (node (ref "U1") (pin "6") (pinfunction "OUT1_6") (pintype "output"))
    )
    (net (code "33") (name "Net-(U1-OUT2)") (class "Default")
      (node (ref "SV1") (pin "5") (pinfunction "5_5") (pintype "passive"))
      (node (ref "U1") (pin "7") (pinfunction "OUT2_7") (pintype "output"))
    )
    (net (code "34") (name "Net-(U1-OUT3)") (class "Default")
      (node (ref "SV1") (pin "7") (pinfunction "7_7") (pintype "passive"))
      (node (ref "U1") (pin "8") (pinfunction "OUT3_8") (pintype "output"))
    )
    (net (code "35") (name "Net-(U1-OUT4)") (class "Default")
      (node (ref "SV1") (pin "9") (pinfunction "9_9") (pintype "passive"))
      (node (ref "U1") (pin "9") (pinfunction "OUT4_9") (pintype "output"))
    )
    (net (code "36") (name "Net-(U1-OUT5)") (class "Default")
      (node (ref "SV1") (pin "11") (pinfunction "11_11") (pintype "passive"))
      (node (ref "U1") (pin "10") (pinfunction "OUT5_10") (pintype "output"))
    )
    (net (code "37") (name "Net-(U1-OUT6)") (class "Default")
      (node (ref "SV1") (pin "13") (pinfunction "13_13") (pintype "passive"))
      (node (ref "U1") (pin "11") (pinfunction "OUT6_11") (pintype "output"))
    )
    (net (code "38") (name "Net-(U1-OUT7)") (class "Default")
      (node (ref "SV1") (pin "15") (pinfunction "15_15") (pintype "passive"))
      (node (ref "U1") (pin "12") (pinfunction "OUT7_12") (pintype "output"))
    )
    (net (code "39") (name "Net-(U1-OUT8)") (class "Default")
      (node (ref "SV1") (pin "2") (pinfunction "2_2") (pintype "passive"))
      (node (ref "U1") (pin "13") (pinfunction "OUT8_13") (pintype "output"))
    )
    (net (code "40") (name "Net-(U1-OUT9)") (class "Default")
      (node (ref "SV1") (pin "4") (pinfunction "4_4") (pintype "passive"))
      (node (ref "U1") (pin "14") (pinfunction "OUT9_14") (pintype "output"))
    )
    (net (code "41") (name "Net-(U1-OUT10)") (class "Default")
      (node (ref "SV1") (pin "6") (pinfunction "6_6") (pintype "passive"))
      (node (ref "U1") (pin "15") (pinfunction "OUT10_15") (pintype "output"))
    )
    (net (code "42") (name "Net-(U1-OUT11)") (class "Default")
      (node (ref "SV1") (pin "8") (pinfunction "8_8") (pintype "passive"))
      (node (ref "U1") (pin "16") (pinfunction "OUT11_16") (pintype "output"))
    )
    (net (code "43") (name "Net-(U1-OUT12)") (class "Default")
      (node (ref "SV1") (pin "10") (pinfunction "10_10") (pintype "passive"))
      (node (ref "U1") (pin "17") (pinfunction "OUT12_17") (pintype "output"))
    )
    (net (code "44") (name "Net-(U1-OUT13)") (class "Default")
      (node (ref "SV1") (pin "12") (pinfunction "12_12") (pintype "passive"))
      (node (ref "U1") (pin "18") (pinfunction "OUT13_18") (pintype "output"))
    )
    (net (code "45") (name "Net-(U1-OUT14)") (class "Default")
      (node (ref "SV1") (pin "14") (pinfunction "14_14") (pintype "passive"))
      (node (ref "U1") (pin "19") (pinfunction "OUT14_19") (pintype "output"))
    )
    (net (code "46") (name "Net-(U1-OUT15)") (class "Default")
      (node (ref "SV1") (pin "16") (pinfunction "16_16") (pintype "passive"))
      (node (ref "U1") (pin "20") (pinfunction "OUT15_20") (pintype "output"))
    )
    (net (code "47") (name "Net-(U1-R-EXT)") (class "Default")
      (node (ref "R2") (pin "2") (pinfunction "2_2") (pintype "passive"))
      (node (ref "U1") (pin "23") (pinfunction "R-EXT_23") (pintype "input"))
    )
    (net (code "48") (name "Net-(U1-SDO)") (class "Default")
      (node (ref "U1") (pin "22") (pinfunction "SDO_22") (pintype "output"))
      (node (ref "U2") (pin "2") (pinfunction "SDI_2") (pintype "input"))
    )
    (net (code "49") (name "Net-(U2-OUT0)") (class "Default")
      (node (ref "SV2") (pin "1") (pinfunction "1_1") (pintype "passive"))
      (node (ref "U2") (pin "5") (pinfunction "OUT0_5") (pintype "output"))
    )
    (net (code "50") (name "Net-(U2-OUT1)") (class "Default")
      (node (ref "SV2") (pin "3") (pinfunction "3_3") (pintype "passive"))
      (node (ref "U2") (pin "6") (pinfunction "OUT1_6") (pintype "output"))
    )
    (net (code "51") (name "Net-(U2-OUT2)") (class "Default")
      (node (ref "SV2") (pin "5") (pinfunction "5_5") (pintype "passive"))
      (node (ref "U2") (pin "7") (pinfunction "OUT2_7") (pintype "output"))
    )
    (net (code "52") (name "Net-(U2-OUT3)") (class "Default")
      (node (ref "SV2") (pin "7") (pinfunction "7_7") (pintype "passive"))
      (node (ref "U2") (pin "8") (pinfunction "OUT3_8") (pintype "output"))
    )
    (net (code "53") (name "Net-(U2-OUT4)") (class "Default")
      (node (ref "SV2") (pin "9") (pinfunction "9_9") (pintype "passive"))
      (node (ref "U2") (pin "9") (pinfunction "OUT4_9") (pintype "output"))
    )
    (net (code "54") (name "Net-(U2-OUT5)") (class "Default")
      (node (ref "SV2") (pin "11") (pinfunction "11_11") (pintype "passive"))
      (node (ref "U2") (pin "10") (pinfunction "OUT5_10") (pintype "output"))
    )
    (net (code "55") (name "Net-(U2-OUT6)") (class "Default")
      (node (ref "SV2") (pin "13") (pinfunction "13_13") (pintype "passive"))
      (node (ref "U2") (pin "11") (pinfunction "OUT6_11") (pintype "output"))
    )
    (net (code "56") (name "Net-(U2-OUT7)") (class "Default")
      (node (ref "SV2") (pin "15") (pinfunction "15_15") (pintype "passive"))
      (node (ref "U2") (pin "12") (pinfunction "OUT7_12") (pintype "output"))
    )
    (net (code "57") (name "Net-(U2-OUT8)") (class "Default")
      (node (ref "SV2") (pin "2") (pinfunction "2_2") (pintype "passive"))
      (node (ref "U2") (pin "13") (pinfunction "OUT8_13") (pintype "output"))
    )
    (net (code "58") (name "Net-(U2-OUT9)") (class "Default")
      (node (ref "SV2") (pin "4") (pinfunction "4_4") (pintype "passive"))
      (node (ref "U2") (pin "14") (pinfunction "OUT9_14") (pintype "output"))
    )
    (net (code "59") (name "Net-(U2-OUT10)") (class "Default")
      (node (ref "SV2") (pin "6") (pinfunction "6_6") (pintype "passive"))
      (node (ref "U2") (pin "15") (pinfunction "OUT10_15") (pintype "output"))
    )
    (net (code "60") (name "Net-(U2-OUT11)") (class "Default")
      (node (ref "SV2") (pin "8") (pinfunction "8_8") (pintype "passive"))
      (node (ref "U2") (pin "16") (pinfunction "OUT11_16") (pintype "output"))
    )
    (net (code "61") (name "Net-(U2-OUT12)") (class "Default")
      (node (ref "SV2") (pin "10") (pinfunction "10_10") (pintype "passive"))
      (node (ref "U2") (pin "17") (pinfunction "OUT12_17") (pintype "output"))
    )
    (net (code "62") (name "Net-(U2-OUT13)") (class "Default")
      (node (ref "SV2") (pin "12") (pinfunction "12_12") (pintype "passive"))
      (node (ref "U2") (pin "18") (pinfunction "OUT13_18") (pintype "output"))
    )
    (net (code "63") (name "Net-(U2-OUT14)") (class "Default")
      (node (ref "SV2") (pin "14") (pinfunction "14_14") (pintype "passive"))
      (node (ref "U2") (pin "19") (pinfunction "OUT14_19") (pintype "output"))
    )
    (net (code "64") (name "Net-(U2-OUT15)") (class "Default")
      (node (ref "SV2") (pin "16") (pinfunction "16_16") (pintype "passive"))
      (node (ref "U2") (pin "20") (pinfunction "OUT15_20") (pintype "output"))
    )
    (net (code "65") (name "Net-(U2-R-EXT)") (class "Default")
      (node (ref "R3") (pin "2") (pinfunction "2_2") (pintype "passive"))
      (node (ref "U2") (pin "23") (pinfunction "R-EXT_23") (pintype "input"))
    )
    (net (code "66") (name "Net-(U2-SDO)") (class "Default")
      (node (ref "U2") (pin "22") (pinfunction "SDO_22") (pintype "output"))
      (node (ref "U3") (pin "2") (pinfunction "SDI_2") (pintype "input"))
    )
    (net (code "67") (name "Net-(U3-OUT0)") (class "Default")
      (node (ref "SV3") (pin "1") (pinfunction "1_1") (pintype "passive"))
      (node (ref "U3") (pin "5") (pinfunction "OUT0_5") (pintype "output"))
    )
    (net (code "68") (name "Net-(U3-OUT1)") (class "Default")
      (node (ref "SV3") (pin "3") (pinfunction "3_3") (pintype "passive"))
      (node (ref "U3") (pin "6") (pinfunction "OUT1_6") (pintype "output"))
    )
    (net (code "69") (name "Net-(U3-OUT2)") (class "Default")
      (node (ref "SV3") (pin "5") (pinfunction "5_5") (pintype "passive"))
      (node (ref "U3") (pin "7") (pinfunction "OUT2_7") (pintype "output"))
    )
    (net (code "70") (name "Net-(U3-OUT3)") (class "Default")
      (node (ref "SV3") (pin "7") (pinfunction "7_7") (pintype "passive"))
      (node (ref "U3") (pin "8") (pinfunction "OUT3_8") (pintype "output"))
    )
    (net (code "71") (name "Net-(U3-OUT4)") (class "Default")
      (node (ref "SV3") (pin "9") (pinfunction "9_9") (pintype "passive"))
      (node (ref "U3") (pin "9") (pinfunction "OUT4_9") (pintype "output"))
    )
    (net (code "72") (name "Net-(U3-OUT5)") (class "Default")
      (node (ref "SV3") (pin "11") (pinfunction "11_11") (pintype "passive"))
      (node (ref "U3") (pin "10") (pinfunction "OUT5_10") (pintype "output"))
    )
    (net (code "73") (name "Net-(U3-OUT6)") (class "Default")
      (node (ref "SV3") (pin "13") (pinfunction "13_13") (pintype "passive"))
      (node (ref "U3") (pin "11") (pinfunction "OUT6_11") (pintype "output"))
    )
    (net (code "74") (name "Net-(U3-OUT7)") (class "Default")
      (node (ref "SV3") (pin "15") (pinfunction "15_15") (pintype "passive"))
      (node (ref "U3") (pin "12") (pinfunction "OUT7_12") (pintype "output"))
    )
    (net (code "75") (name "Net-(U3-OUT8)") (class "Default")
      (node (ref "SV3") (pin "2") (pinfunction "2_2") (pintype "passive"))
      (node (ref "U3") (pin "13") (pinfunction "OUT8_13") (pintype "output"))
    )
    (net (code "76") (name "Net-(U3-OUT9)") (class "Default")
      (node (ref "SV3") (pin "4") (pinfunction "4_4") (pintype "passive"))
      (node (ref "U3") (pin "14") (pinfunction "OUT9_14") (pintype "output"))
    )
    (net (code "77") (name "Net-(U3-OUT10)") (class "Default")
      (node (ref "SV3") (pin "6") (pinfunction "6_6") (pintype "passive"))
      (node (ref "U3") (pin "15") (pinfunction "OUT10_15") (pintype "output"))
    )
    (net (code "78") (name "Net-(U3-OUT11)") (class "Default")
      (node (ref "SV3") (pin "8") (pinfunction "8_8") (pintype "passive"))
      (node (ref "U3") (pin "16") (pinfunction "OUT11_16") (pintype "output"))
    )
    (net (code "79") (name "Net-(U3-OUT12)") (class "Default")
      (node (ref "SV3") (pin "10") (pinfunction "10_10") (pintype "passive"))
      (node (ref "U3") (pin "17") (pinfunction "OUT12_17") (pintype "output"))
    )
    (net (code "80") (name "Net-(U3-OUT13)") (class "Default")
      (node (ref "SV3") (pin "12") (pinfunction "12_12") (pintype "passive"))
      (node (ref "U3") (pin "18") (pinfunction "OUT13_18") (pintype "output"))
    )
    (net (code "81") (name "Net-(U3-OUT14)") (class "Default")
      (node (ref "SV3") (pin "14") (pinfunction "14_14") (pintype "passive"))
      (node (ref "U3") (pin "19") (pinfunction "OUT14_19") (pintype "output"))
    )
    (net (code "82") (name "Net-(U3-OUT15)") (class "Default")
      (node (ref "SV3") (pin "16") (pinfunction "16_16") (pintype "passive"))
      (node (ref "U3") (pin "20") (pinfunction "OUT15_20") (pintype "output"))
    )
    (net (code "83") (name "Net-(U3-R-EXT)") (class "Default")
      (node (ref "R4") (pin "2") (pinfunction "2_2") (pintype "passive"))
      (node (ref "U3") (pin "23") (pinfunction "R-EXT_23") (pintype "input"))
    )
    (net (code "84") (name "Net-(U3-SDO)") (class "Default")
      (node (ref "U3") (pin "22") (pinfunction "SDO_22") (pintype "output"))
      (node (ref "U4") (pin "2") (pinfunction "SDI_2") (pintype "input"))
    )
    (net (code "85") (name "Net-(U4-OUT0)") (class "Default")
      (node (ref "SV4") (pin "1") (pinfunction "1_1") (pintype "passive"))
      (node (ref "U4") (pin "5") (pinfunction "OUT0_5") (pintype "output"))
    )
    (net (code "86") (name "Net-(U4-OUT1)") (class "Default")
      (node (ref "SV4") (pin "3") (pinfunction "3_3") (pintype "passive"))
      (node (ref "U4") (pin "6") (pinfunction "OUT1_6") (pintype "output"))
    )
    (net (code "87") (name "Net-(U4-OUT2)") (class "Default")
      (node (ref "SV4") (pin "5") (pinfunction "5_5") (pintype "passive"))
      (node (ref "U4") (pin "7") (pinfunction "OUT2_7") (pintype "output"))
    )
    (net (code "88") (name "Net-(U4-OUT3)") (class "Default")
      (node (ref "SV4") (pin "7") (pinfunction "7_7") (pintype "passive"))
      (node (ref "U4") (pin "8") (pinfunction "OUT3_8") (pintype "output"))
    )
    (net (code "89") (name "Net-(U4-OUT4)") (class "Default")
      (node (ref "SV4") (pin "9") (pinfunction "9_9") (pintype "passive"))
      (node (ref "U4") (pin "9") (pinfunction "OUT4_9") (pintype "output"))
    )
    (net (code "90") (name "Net-(U4-OUT5)") (class "Default")
      (node (ref "SV4") (pin "11") (pinfunction "11_11") (pintype "passive"))
      (node (ref "U4") (pin "10") (pinfunction "OUT5_10") (pintype "output"))
    )
    (net (code "91") (name "Net-(U4-OUT6)") (class "Default")
      (node (ref "SV4") (pin "13") (pinfunction "13_13") (pintype "passive"))
      (node (ref "U4") (pin "11") (pinfunction "OUT6_11") (pintype "output"))
    )
    (net (code "92") (name "Net-(U4-OUT7)") (class "Default")
      (node (ref "SV4") (pin "15") (pinfunction "15_15") (pintype "passive"))
      (node (ref "U4") (pin "12") (pinfunction "OUT7_12") (pintype "output"))
    )
    (net (code "93") (name "Net-(U4-OUT8)") (class "Default")
      (node (ref "SV4") (pin "2") (pinfunction "2_2") (pintype "passive"))
      (node (ref "U4") (pin "13") (pinfunction "OUT8_13") (pintype "output"))
    )
    (net (code "94") (name "Net-(U4-OUT9)") (class "Default")
      (node (ref "SV4") (pin "4") (pinfunction "4_4") (pintype "passive"))
      (node (ref "U4") (pin "14") (pinfunction "OUT9_14") (pintype "output"))
    )
    (net (code "95") (name "Net-(U4-OUT10)") (class "Default")
      (node (ref "SV4") (pin "6") (pinfunction "6_6") (pintype "passive"))
      (node (ref "U4") (pin "15") (pinfunction "OUT10_15") (pintype "output"))
    )
    (net (code "96") (name "Net-(U4-OUT11)") (class "Default")
      (node (ref "SV4") (pin "8") (pinfunction "8_8") (pintype "passive"))
      (node (ref "U4") (pin "16") (pinfunction "OUT11_16") (pintype "output"))
    )
    (net (code "97") (name "Net-(U4-OUT12)") (class "Default")
      (node (ref "SV4") (pin "10") (pinfunction "10_10") (pintype "passive"))
      (node (ref "U4") (pin "17") (pinfunction "OUT12_17") (pintype "output"))
    )
    (net (code "98") (name "Net-(U4-OUT13)") (class "Default")
      (node (ref "SV4") (pin "12") (pinfunction "12_12") (pintype "passive"))
      (node (ref "U4") (pin "18") (pinfunction "OUT13_18") (pintype "output"))
    )
    (net (code "99") (name "Net-(U4-OUT14)") (class "Default")
      (node (ref "SV4") (pin "14") (pinfunction "14_14") (pintype "passive"))
      (node (ref "U4") (pin "19") (pinfunction "OUT14_19") (pintype "output"))
    )
    (net (code "100") (name "Net-(U4-OUT15)") (class "Default")
      (node (ref "SV4") (pin "16") (pinfunction "16_16") (pintype "passive"))
      (node (ref "U4") (pin "20") (pinfunction "OUT15_20") (pintype "output"))
    )
    (net (code "101") (name "Net-(U4-R-EXT)") (class "Default")
      (node (ref "R5") (pin "2") (pinfunction "2_2") (pintype "passive"))
      (node (ref "U4") (pin "23") (pinfunction "R-EXT_23") (pintype "input"))
    )
    (net (code "102") (name "Net-(U5-OUT0)") (class "Default")
      (node (ref "SV5") (pin "1") (pinfunction "1_1") (pintype "passive"))
      (node (ref "U5") (pin "5") (pinfunction "OUT0_5") (pintype "output"))
    )
    (net (code "103") (name "Net-(U5-OUT1)") (class "Default")
      (node (ref "SV5") (pin "3") (pinfunction "3_3") (pintype "passive"))
      (node (ref "U5") (pin "6") (pinfunction "OUT1_6") (pintype "output"))
    )
    (net (code "104") (name "Net-(U5-OUT2)") (class "Default")
      (node (ref "SV5") (pin "5") (pinfunction "5_5") (pintype "passive"))
      (node (ref "U5") (pin "7") (pinfunction "OUT2_7") (pintype "output"))
    )
    (net (code "105") (name "Net-(U5-OUT3)") (class "Default")
      (node (ref "SV5") (pin "7") (pinfunction "7_7") (pintype "passive"))
      (node (ref "U5") (pin "8") (pinfunction "OUT3_8") (pintype "output"))
    )
    (net (code "106") (name "Net-(U5-OUT4)") (class "Default")
      (node (ref "SV5") (pin "9") (pinfunction "9_9") (pintype "passive"))
      (node (ref "U5") (pin "9") (pinfunction "OUT4_9") (pintype "output"))
    )
    (net (code "107") (name "Net-(U5-OUT5)") (class "Default")
      (node (ref "SV5") (pin "11") (pinfunction "11_11") (pintype "passive"))
      (node (ref "U5") (pin "10") (pinfunction "OUT5_10") (pintype "output"))
    )
    (net (code "108") (name "Net-(U5-OUT6)") (class "Default")
      (node (ref "SV5") (pin "13") (pinfunction "13_13") (pintype "passive"))
      (node (ref "U5") (pin "11") (pinfunction "OUT6_11") (pintype "output"))
    )
    (net (code "109") (name "Net-(U5-OUT7)") (class "Default")
      (node (ref "SV5") (pin "15") (pinfunction "15_15") (pintype "passive"))
      (node (ref "U5") (pin "12") (pinfunction "OUT7_12") (pintype "output"))
    )
    (net (code "110") (name "Net-(U5-OUT8)") (class "Default")
      (node (ref "SV5") (pin "2") (pinfunction "2_2") (pintype "passive"))
      (node (ref "U5") (pin "13") (pinfunction "OUT8_13") (pintype "output"))
    )
    (net (code "111") (name "Net-(U5-OUT9)") (class "Default")
      (node (ref "SV5") (pin "4") (pinfunction "4_4") (pintype "passive"))
      (node (ref "U5") (pin "14") (pinfunction "OUT9_14") (pintype "output"))
    )
    (net (code "112") (name "Net-(U5-OUT10)") (class "Default")
      (node (ref "SV5") (pin "6") (pinfunction "6_6") (pintype "passive"))
      (node (ref "U5") (pin "15") (pinfunction "OUT10_15") (pintype "output"))
    )
    (net (code "113") (name "Net-(U5-OUT11)") (class "Default")
      (node (ref "SV5") (pin "8") (pinfunction "8_8") (pintype "passive"))
      (node (ref "U5") (pin "16") (pinfunction "OUT11_16") (pintype "output"))
    )
    (net (code "114") (name "Net-(U5-OUT12)") (class "Default")
      (node (ref "SV5") (pin "10") (pinfunction "10_10") (pintype "passive"))
      (node (ref "U5") (pin "17") (pinfunction "OUT12_17") (pintype "output"))
    )
    (net (code "115") (name "Net-(U5-OUT13)") (class "Default")
      (node (ref "SV5") (pin "12") (pinfunction "12_12") (pintype "passive"))
      (node (ref "U5") (pin "18") (pinfunction "OUT13_18") (pintype "output"))
    )
    (net (code "116") (name "Net-(U5-OUT14)") (class "Default")
      (node (ref "SV5") (pin "14") (pinfunction "14_14") (pintype "passive"))
      (node (ref "U5") (pin "19") (pinfunction "OUT14_19") (pintype "output"))
    )
    (net (code "117") (name "Net-(U5-OUT15)") (class "Default")
      (node (ref "SV5") (pin "16") (pinfunction "16_16") (pintype "passive"))
      (node (ref "U5") (pin "20") (pinfunction "OUT15_20") (pintype "output"))
    )
    (net (code "118") (name "Net-(U5-R-EXT)") (class "Default")
      (node (ref "R6") (pin "2") (pinfunction "2_2") (pintype "passive"))
      (node (ref "U5") (pin "23") (pinfunction "R-EXT_23") (pintype "input"))
    )
    (net (code "119") (name "Net-(U5-SDO)") (class "Default")
      (node (ref "U5") (pin "22") (pinfunction "SDO_22") (pintype "output"))
      (node (ref "U6") (pin "2") (pinfunction "SDI_2") (pintype "input"))
    )
    (net (code "120") (name "Net-(U6-OUT0)") (class "Default")
      (node (ref "SV6") (pin "1") (pinfunction "1_1") (pintype "passive"))
      (node (ref "U6") (pin "5") (pinfunction "OUT0_5") (pintype "output"))
    )
    (net (code "121") (name "Net-(U6-OUT1)") (class "Default")
      (node (ref "SV6") (pin "3") (pinfunction "3_3") (pintype "passive"))
      (node (ref "U6") (pin "6") (pinfunction "OUT1_6") (pintype "output"))
    )
    (net (code "122") (name "Net-(U6-OUT2)") (class "Default")
      (node (ref "SV6") (pin "5") (pinfunction "5_5") (pintype "passive"))
      (node (ref "U6") (pin "7") (pinfunction "OUT2_7") (pintype "output"))
    )
    (net (code "123") (name "Net-(U6-OUT3)") (class "Default")
      (node (ref "SV6") (pin "7") (pinfunction "7_7") (pintype "passive"))
      (node (ref "U6") (pin "8") (pinfunction "OUT3_8") (pintype "output"))
    )
    (net (code "124") (name "Net-(U6-OUT4)") (class "Default")
      (node (ref "SV6") (pin "9") (pinfunction "9_9") (pintype "passive"))
      (node (ref "U6") (pin "9") (pinfunction "OUT4_9") (pintype "output"))
    )
    (net (code "125") (name "Net-(U6-OUT5)") (class "Default")
      (node (ref "SV6") (pin "11") (pinfunction "11_11") (pintype "passive"))
      (node (ref "U6") (pin "10") (pinfunction "OUT5_10") (pintype "output"))
    )
    (net (code "126") (name "Net-(U6-OUT6)") (class "Default")
      (node (ref "SV6") (pin "13") (pinfunction "13_13") (pintype "passive"))
      (node (ref "U6") (pin "11") (pinfunction "OUT6_11") (pintype "output"))
    )
    (net (code "127") (name "Net-(U6-OUT7)") (class "Default")
      (node (ref "SV6") (pin "15") (pinfunction "15_15") (pintype "passive"))
      (node (ref "U6") (pin "12") (pinfunction "OUT7_12") (pintype "output"))
    )
    (net (code "128") (name "Net-(U6-OUT8)") (class "Default")
      (node (ref "SV6") (pin "2") (pinfunction "2_2") (pintype "passive"))
      (node (ref "U6") (pin "13") (pinfunction "OUT8_13") (pintype "output"))
    )
    (net (code "129") (name "Net-(U6-OUT9)") (class "Default")
      (node (ref "SV6") (pin "4") (pinfunction "4_4") (pintype "passive"))
      (node (ref "U6") (pin "14") (pinfunction "OUT9_14") (pintype "output"))
    )
    (net (code "130") (name "Net-(U6-OUT10)") (class "Default")
      (node (ref "SV6") (pin "6") (pinfunction "6_6") (pintype "passive"))
      (node (ref "U6") (pin "15") (pinfunction "OUT10_15") (pintype "output"))
    )
    (net (code "131") (name "Net-(U6-OUT11)") (class "Default")
      (node (ref "SV6") (pin "8") (pinfunction "8_8") (pintype "passive"))
      (node (ref "U6") (pin "16") (pinfunction "OUT11_16") (pintype "output"))
    )
    (net (code "132") (name "Net-(U6-OUT12)") (class "Default")
      (node (ref "SV6") (pin "10") (pinfunction "10_10") (pintype "passive"))
      (node (ref "U6") (pin "17") (pinfunction "OUT12_17") (pintype "output"))
    )
    (net (code "133") (name "Net-(U6-OUT13)") (class "Default")
      (node (ref "SV6") (pin "12") (pinfunction "12_12") (pintype "passive"))
      (node (ref "U6") (pin "18") (pinfunction "OUT13_18") (pintype "output"))
    )
    (net (code "134") (name "Net-(U6-OUT14)") (class "Default")
      (node (ref "SV6") (pin "14") (pinfunction "14_14") (pintype "passive"))
      (node (ref "U6") (pin "19") (pinfunction "OUT14_19") (pintype "output"))
    )
    (net (code "135") (name "Net-(U6-OUT15)") (class "Default")
      (node (ref "SV6") (pin "16") (pinfunction "16_16") (pintype "passive"))
      (node (ref "U6") (pin "20") (pinfunction "OUT15_20") (pintype "output"))
    )
    (net (code "136") (name "Net-(U6-R-EXT)") (class "Default")
      (node (ref "R7") (pin "2") (pinfunction "2_2") (pintype "passive"))
      (node (ref "U6") (pin "23") (pinfunction "R-EXT_23") (pintype "input"))
    )
    (net (code "137") (name "Net-(U6-SDO)") (class "Default")
      (node (ref "U6") (pin "22") (pinfunction "SDO_22") (pintype "output"))
      (node (ref "U7") (pin "2") (pinfunction "SDI_2") (pintype "input"))
    )
    (net (code "138") (name "Net-(U7-OUT0)") (class "Default")
      (node (ref "SV7") (pin "1") (pinfunction "1_1") (pintype "passive"))
      (node (ref "U7") (pin "5") (pinfunction "OUT0_5") (pintype "output"))
    )
    (net (code "139") (name "Net-(U7-OUT1)") (class "Default")
      (node (ref "SV7") (pin "3") (pinfunction "3_3") (pintype "passive"))
      (node (ref "U7") (pin "6") (pinfunction "OUT1_6") (pintype "output"))
    )
    (net (code "140") (name "Net-(U7-OUT2)") (class "Default")
      (node (ref "SV7") (pin "5") (pinfunction "5_5") (pintype "passive"))
      (node (ref "U7") (pin "7") (pinfunction "OUT2_7") (pintype "output"))
    )
    (net (code "141") (name "Net-(U7-OUT3)") (class "Default")
      (node (ref "SV7") (pin "7") (pinfunction "7_7") (pintype "passive"))
      (node (ref "U7") (pin "8") (pinfunction "OUT3_8") (pintype "output"))
    )
    (net (code "142") (name "Net-(U7-OUT4)") (class "Default")
      (node (ref "SV7") (pin "9") (pinfunction "9_9") (pintype "passive"))
      (node (ref "U7") (pin "9") (pinfunction "OUT4_9") (pintype "output"))
    )
    (net (code "143") (name "Net-(U7-OUT5)") (class "Default")
      (node (ref "SV7") (pin "11") (pinfunction "11_11") (pintype "passive"))
      (node (ref "U7") (pin "10") (pinfunction "OUT5_10") (pintype "output"))
    )
    (net (code "144") (name "Net-(U7-OUT6)") (class "Default")
      (node (ref "SV7") (pin "13") (pinfunction "13_13") (pintype "passive"))
      (node (ref "U7") (pin "11") (pinfunction "OUT6_11") (pintype "output"))
    )
    (net (code "145") (name "Net-(U7-OUT7)") (class "Default")
      (node (ref "SV7") (pin "15") (pinfunction "15_15") (pintype "passive"))
      (node (ref "U7") (pin "12") (pinfunction "OUT7_12") (pintype "output"))
    )
    (net (code "146") (name "Net-(U7-OUT8)") (class "Default")
      (node (ref "SV7") (pin "2") (pinfunction "2_2") (pintype "passive"))
      (node (ref "U7") (pin "13") (pinfunction "OUT8_13") (pintype "output"))
    )
    (net (code "147") (name "Net-(U7-OUT9)") (class "Default")
      (node (ref "SV7") (pin "4") (pinfunction "4_4") (pintype "passive"))
      (node (ref "U7") (pin "14") (pinfunction "OUT9_14") (pintype "output"))
    )
    (net (code "148") (name "Net-(U7-OUT10)") (class "Default")
      (node (ref "SV7") (pin "6") (pinfunction "6_6") (pintype "passive"))
      (node (ref "U7") (pin "15") (pinfunction "OUT10_15") (pintype "output"))
    )
    (net (code "149") (name "Net-(U7-OUT11)") (class "Default")
      (node (ref "SV7") (pin "8") (pinfunction "8_8") (pintype "passive"))
      (node (ref "U7") (pin "16") (pinfunction "OUT11_16") (pintype "output"))
    )
    (net (code "150") (name "Net-(U7-OUT12)") (class "Default")
      (node (ref "SV7") (pin "10") (pinfunction "10_10") (pintype "passive"))
      (node (ref "U7") (pin "17") (pinfunction "OUT12_17") (pintype "output"))
    )
    (net (code "151") (name "Net-(U7-OUT13)") (class "Default")
      (node (ref "SV7") (pin "12") (pinfunction "12_12") (pintype "passive"))
      (node (ref "U7") (pin "18") (pinfunction "OUT13_18") (pintype "output"))
    )
    (net (code "152") (name "Net-(U7-OUT14)") (class "Default")
      (node (ref "SV7") (pin "14") (pinfunction "14_14") (pintype "passive"))
      (node (ref "U7") (pin "19") (pinfunction "OUT14_19") (pintype "output"))
    )
    (net (code "153") (name "Net-(U7-OUT15)") (class "Default")
      (node (ref "SV7") (pin "16") (pinfunction "16_16") (pintype "passive"))
      (node (ref "U7") (pin "20") (pinfunction "OUT15_20") (pintype "output"))
    )
    (net (code "154") (name "Net-(U7-R-EXT)") (class "Default")
      (node (ref "R8") (pin "2") (pinfunction "2_2") (pintype "passive"))
      (node (ref "U7") (pin "23") (pinfunction "R-EXT_23") (pintype "input"))
    )
    (net (code "155") (name "Net-(U7-SDO)") (class "Default")
      (node (ref "U7") (pin "22") (pinfunction "SDO_22") (pintype "output"))
      (node (ref "U8") (pin "2") (pinfunction "SDI_2") (pintype "input"))
    )
    (net (code "156") (name "Net-(U8-OUT0)") (class "Default")
      (node (ref "SV8") (pin "1") (pinfunction "1_1") (pintype "passive"))
      (node (ref "U8") (pin "5") (pinfunction "OUT0_5") (pintype "output"))
    )
    (net (code "157") (name "Net-(U8-OUT1)") (class "Default")
      (node (ref "SV8") (pin "3") (pinfunction "3_3") (pintype "passive"))
      (node (ref "U8") (pin "6") (pinfunction "OUT1_6") (pintype "output"))
    )
    (net (code "158") (name "Net-(U8-OUT2)") (class "Default")
      (node (ref "SV8") (pin "5") (pinfunction "5_5") (pintype "passive"))
      (node (ref "U8") (pin "7") (pinfunction "OUT2_7") (pintype "output"))
    )
    (net (code "159") (name "Net-(U8-OUT3)") (class "Default")
      (node (ref "SV8") (pin "7") (pinfunction "7_7") (pintype "passive"))
      (node (ref "U8") (pin "8") (pinfunction "OUT3_8") (pintype "output"))
    )
    (net (code "160") (name "Net-(U8-OUT4)") (class "Default")
      (node (ref "SV8") (pin "9") (pinfunction "9_9") (pintype "passive"))
      (node (ref "U8") (pin "9") (pinfunction "OUT4_9") (pintype "output"))
    )
    (net (code "161") (name "Net-(U8-OUT5)") (class "Default")
      (node (ref "SV8") (pin "11") (pinfunction "11_11") (pintype "passive"))
      (node (ref "U8") (pin "10") (pinfunction "OUT5_10") (pintype "output"))
    )
    (net (code "162") (name "Net-(U8-OUT6)") (class "Default")
      (node (ref "SV8") (pin "13") (pinfunction "13_13") (pintype "passive"))
      (node (ref "U8") (pin "11") (pinfunction "OUT6_11") (pintype "output"))
    )
    (net (code "163") (name "Net-(U8-OUT7)") (class "Default")
      (node (ref "SV8") (pin "15") (pinfunction "15_15") (pintype "passive"))
      (node (ref "U8") (pin "12") (pinfunction "OUT7_12") (pintype "output"))
    )
    (net (code "164") (name "Net-(U8-OUT8)") (class "Default")
      (node (ref "SV8") (pin "2") (pinfunction "2_2") (pintype "passive"))
      (node (ref "U8") (pin "13") (pinfunction "OUT8_13") (pintype "output"))
    )
    (net (code "165") (name "Net-(U8-OUT9)") (class "Default")
      (node (ref "SV8") (pin "4") (pinfunction "4_4") (pintype "passive"))
      (node (ref "U8") (pin "14") (pinfunction "OUT9_14") (pintype "output"))
    )
    (net (code "166") (name "Net-(U8-OUT10)") (class "Default")
      (node (ref "SV8") (pin "6") (pinfunction "6_6") (pintype "passive"))
      (node (ref "U8") (pin "15") (pinfunction "OUT10_15") (pintype "output"))
    )
    (net (code "167") (name "Net-(U8-OUT11)") (class "Default")
      (node (ref "SV8") (pin "8") (pinfunction "8_8") (pintype "passive"))
      (node (ref "U8") (pin "16") (pinfunction "OUT11_16") (pintype "output"))
    )
    (net (code "168") (name "Net-(U8-OUT12)") (class "Default")
      (node (ref "SV8") (pin "10") (pinfunction "10_10") (pintype "passive"))
      (node (ref "U8") (pin "17") (pinfunction "OUT12_17") (pintype "output"))
    )
    (net (code "169") (name "Net-(U8-OUT13)") (class "Default")
      (node (ref "SV8") (pin "12") (pinfunction "12_12") (pintype "passive"))
      (node (ref "U8") (pin "18") (pinfunction "OUT13_18") (pintype "output"))
    )
    (net (code "170") (name "Net-(U8-OUT14)") (class "Default")
      (node (ref "SV8") (pin "14") (pinfunction "14_14") (pintype "passive"))
      (node (ref "U8") (pin "19") (pinfunction "OUT14_19") (pintype "output"))
    )
    (net (code "171") (name "Net-(U8-OUT15)") (class "Default")
      (node (ref "SV8") (pin "16") (pinfunction "16_16") (pintype "passive"))
      (node (ref "U8") (pin "20") (pinfunction "OUT15_20") (pintype "output"))
    )
    (net (code "172") (name "Net-(U8-R-EXT)") (class "Default")
      (node (ref "R9") (pin "2") (pinfunction "2_2") (pintype "passive"))
      (node (ref "U8") (pin "23") (pinfunction "R-EXT_23") (pintype "input"))
    )
    (net (code "173") (name "Net-(U9-OUT0)") (class "Default")
      (node (ref "SV9") (pin "1") (pinfunction "1_1") (pintype "passive"))
      (node (ref "U9") (pin "5") (pinfunction "OUT0_5") (pintype "output"))
    )
    (net (code "174") (name "Net-(U9-OUT1)") (class "Default")
      (node (ref "SV9") (pin "3") (pinfunction "3_3") (pintype "passive"))
      (node (ref "U9") (pin "6") (pinfunction "OUT1_6") (pintype "output"))
    )
    (net (code "175") (name "Net-(U9-OUT2)") (class "Default")
      (node (ref "SV9") (pin "5") (pinfunction "5_5") (pintype "passive"))
      (node (ref "U9") (pin "7") (pinfunction "OUT2_7") (pintype "output"))
    )
    (net (code "176") (name "Net-(U9-OUT3)") (class "Default")
      (node (ref "SV9") (pin "7") (pinfunction "7_7") (pintype "passive"))
      (node (ref "U9") (pin "8") (pinfunction "OUT3_8") (pintype "output"))
    )
    (net (code "177") (name "Net-(U9-OUT4)") (class "Default")
      (node (ref "SV9") (pin "9") (pinfunction "9_9") (pintype "passive"))
      (node (ref "U9") (pin "9") (pinfunction "OUT4_9") (pintype "output"))
    )
    (net (code "178") (name "Net-(U9-OUT5)") (class "Default")
      (node (ref "SV9") (pin "11") (pinfunction "11_11") (pintype "passive"))
      (node (ref "U9") (pin "10") (pinfunction "OUT5_10") (pintype "output"))
    )
    (net (code "179") (name "Net-(U9-OUT6)") (class "Default")
      (node (ref "SV9") (pin "13") (pinfunction "13_13") (pintype "passive"))
      (node (ref "U9") (pin "11") (pinfunction "OUT6_11") (pintype "output"))
    )
    (net (code "180") (name "Net-(U9-OUT7)") (class "Default")
      (node (ref "SV9") (pin "15") (pinfunction "15_15") (pintype "passive"))
      (node (ref "U9") (pin "12") (pinfunction "OUT7_12") (pintype "output"))
    )
    (net (code "181") (name "Net-(U9-OUT8)") (class "Default")
      (node (ref "SV9") (pin "2") (pinfunction "2_2") (pintype "passive"))
      (node (ref "U9") (pin "13") (pinfunction "OUT8_13") (pintype "output"))
    )
    (net (code "182") (name "Net-(U9-OUT9)") (class "Default")
      (node (ref "SV9") (pin "4") (pinfunction "4_4") (pintype "passive"))
      (node (ref "U9") (pin "14") (pinfunction "OUT9_14") (pintype "output"))
    )
    (net (code "183") (name "Net-(U9-OUT10)") (class "Default")
      (node (ref "SV9") (pin "6") (pinfunction "6_6") (pintype "passive"))
      (node (ref "U9") (pin "15") (pinfunction "OUT10_15") (pintype "output"))
    )
    (net (code "184") (name "Net-(U9-OUT11)") (class "Default")
      (node (ref "SV9") (pin "8") (pinfunction "8_8") (pintype "passive"))
      (node (ref "U9") (pin "16") (pinfunction "OUT11_16") (pintype "output"))
    )
    (net (code "185") (name "Net-(U9-OUT12)") (class "Default")
      (node (ref "SV9") (pin "10") (pinfunction "10_10") (pintype "passive"))
      (node (ref "U9") (pin "17") (pinfunction "OUT12_17") (pintype "output"))
    )
    (net (code "186") (name "Net-(U9-OUT13)") (class "Default")
      (node (ref "SV9") (pin "12") (pinfunction "12_12") (pintype "passive"))
      (node (ref "U9") (pin "18") (pinfunction "OUT13_18") (pintype "output"))
    )
    (net (code "187") (name "Net-(U9-OUT14)") (class "Default")
      (node (ref "SV9") (pin "14") (pinfunction "14_14") (pintype "passive"))
      (node (ref "U9") (pin "19") (pinfunction "OUT14_19") (pintype "output"))
    )
    (net (code "188") (name "Net-(U9-OUT15)") (class "Default")
      (node (ref "SV9") (pin "16") (pinfunction "16_16") (pintype "passive"))
      (node (ref "U9") (pin "20") (pinfunction "OUT15_20") (pintype "output"))
    )
    (net (code "189") (name "Net-(U9-R-EXT)") (class "Default")
      (node (ref "R10") (pin "2") (pinfunction "2_2") (pintype "passive"))
      (node (ref "U9") (pin "23") (pinfunction "R-EXT_23") (pintype "input"))
    )
    (net (code "190") (name "Net-(U10-OUT0)") (class "Default")
      (node (ref "SV10") (pin "1") (pinfunction "1_1") (pintype "passive"))
      (node (ref "U10") (pin "5") (pinfunction "OUT0_5") (pintype "output"))
    )
    (net (code "191") (name "Net-(U10-OUT1)") (class "Default")
      (node (ref "SV10") (pin "3") (pinfunction "3_3") (pintype "passive"))
      (node (ref "U10") (pin "6") (pinfunction "OUT1_6") (pintype "output"))
    )
    (net (code "192") (name "Net-(U10-OUT2)") (class "Default")
      (node (ref "SV10") (pin "5") (pinfunction "5_5") (pintype "passive"))
      (node (ref "U10") (pin "7") (pinfunction "OUT2_7") (pintype "output"))
    )
    (net (code "193") (name "Net-(U10-OUT3)") (class "Default")
      (node (ref "SV10") (pin "7") (pinfunction "7_7") (pintype "passive"))
      (node (ref "U10") (pin "8") (pinfunction "OUT3_8") (pintype "output"))
    )
    (net (code "194") (name "Net-(U10-OUT4)") (class "Default")
      (node (ref "SV10") (pin "9") (pinfunction "9_9") (pintype "passive"))
      (node (ref "U10") (pin "9") (pinfunction "OUT4_9") (pintype "output"))
    )
    (net (code "195") (name "Net-(U10-OUT5)") (class "Default")
      (node (ref "SV10") (pin "11") (pinfunction "11_11") (pintype "passive"))
      (node (ref "U10") (pin "10") (pinfunction "OUT5_10") (pintype "output"))
    )
    (net (code "196") (name "Net-(U10-OUT6)") (class "Default")
      (node (ref "SV10") (pin "13") (pinfunction "13_13") (pintype "passive"))
      (node (ref "U10") (pin "11") (pinfunction "OUT6_11") (pintype "output"))
    )
    (net (code "197") (name "Net-(U10-OUT7)") (class "Default")
      (node (ref "SV10") (pin "15") (pinfunction "15_15") (pintype "passive"))
      (node (ref "U10") (pin "12") (pinfunction "OUT7_12") (pintype "output"))
    )
    (net (code "198") (name "Net-(U10-OUT8)") (class "Default")
      (node (ref "SV10") (pin "2") (pinfunction "2_2") (pintype "passive"))
      (node (ref "U10") (pin "13") (pinfunction "OUT8_13") (pintype "output"))
    )
    (net (code "199") (name "Net-(U10-OUT9)") (class "Default")
      (node (ref "SV10") (pin "4") (pinfunction "4_4") (pintype "passive"))
      (node (ref "U10") (pin "14") (pinfunction "OUT9_14") (pintype "output"))
    )
    (net (code "200") (name "Net-(U10-OUT10)") (class "Default")
      (node (ref "SV10") (pin "6") (pinfunction "6_6") (pintype "passive"))
      (node (ref "U10") (pin "15") (pinfunction "OUT10_15") (pintype "output"))
    )
    (net (code "201") (name "Net-(U10-OUT11)") (class "Default")
      (node (ref "SV10") (pin "8") (pinfunction "8_8") (pintype "passive"))
      (node (ref "U10") (pin "16") (pinfunction "OUT11_16") (pintype "output"))
    )
    (net (code "202") (name "Net-(U10-OUT12)") (class "Default")
      (node (ref "SV10") (pin "10") (pinfunction "10_10") (pintype "passive"))
      (node (ref "U10") (pin "17") (pinfunction "OUT12_17") (pintype "output"))
    )
    (net (code "203") (name "Net-(U10-OUT13)") (class "Default")
      (node (ref "SV10") (pin "12") (pinfunction "12_12") (pintype "passive"))
      (node (ref "U10") (pin "18") (pinfunction "OUT13_18") (pintype "output"))
    )
    (net (code "204") (name "Net-(U10-OUT14)") (class "Default")
      (node (ref "SV10") (pin "14") (pinfunction "14_14") (pintype "passive"))
      (node (ref "U10") (pin "19") (pinfunction "OUT14_19") (pintype "output"))
    )
    (net (code "205") (name "Net-(U10-OUT15)") (class "Default")
      (node (ref "SV10") (pin "16") (pinfunction "16_16") (pintype "passive"))
      (node (ref "U10") (pin "20") (pinfunction "OUT15_20") (pintype "output"))
    )
    (net (code "206") (name "Net-(U10-R-EXT)") (class "Default")
      (node (ref "R11") (pin "2") (pinfunction "2_2") (pintype "passive"))
      (node (ref "U10") (pin "23") (pinfunction "R-EXT_23") (pintype "input"))
    )
    (net (code "207") (name "Net-(U10-SDI)") (class "Default")
      (node (ref "U10") (pin "2") (pinfunction "SDI_2") (pintype "input"))
      (node (ref "U9") (pin "22") (pinfunction "SDO_22") (pintype "output"))
    )
    (net (code "208") (name "Net-(U10-SDO)") (class "Default")
      (node (ref "U10") (pin "22") (pinfunction "SDO_22") (pintype "output"))
      (node (ref "U11") (pin "2") (pinfunction "SDI_2") (pintype "input"))
    )
    (net (code "209") (name "Net-(U11-OUT0)") (class "Default")
      (node (ref "SV11") (pin "1") (pinfunction "1_1") (pintype "passive"))
      (node (ref "U11") (pin "5") (pinfunction "OUT0_5") (pintype "output"))
    )
    (net (code "210") (name "Net-(U11-OUT1)") (class "Default")
      (node (ref "SV11") (pin "3") (pinfunction "3_3") (pintype "passive"))
      (node (ref "U11") (pin "6") (pinfunction "OUT1_6") (pintype "output"))
    )
    (net (code "211") (name "Net-(U11-OUT2)") (class "Default")
      (node (ref "SV11") (pin "5") (pinfunction "5_5") (pintype "passive"))
      (node (ref "U11") (pin "7") (pinfunction "OUT2_7") (pintype "output"))
    )
    (net (code "212") (name "Net-(U11-OUT3)") (class "Default")
      (node (ref "SV11") (pin "7") (pinfunction "7_7") (pintype "passive"))
      (node (ref "U11") (pin "8") (pinfunction "OUT3_8") (pintype "output"))
    )
    (net (code "213") (name "Net-(U11-OUT4)") (class "Default")
      (node (ref "SV11") (pin "9") (pinfunction "9_9") (pintype "passive"))
      (node (ref "U11") (pin "9") (pinfunction "OUT4_9") (pintype "output"))
    )
    (net (code "214") (name "Net-(U11-OUT5)") (class "Default")
      (node (ref "SV11") (pin "11") (pinfunction "11_11") (pintype "passive"))
      (node (ref "U11") (pin "10") (pinfunction "OUT5_10") (pintype "output"))
    )
    (net (code "215") (name "Net-(U11-OUT6)") (class "Default")
      (node (ref "SV11") (pin "13") (pinfunction "13_13") (pintype "passive"))
      (node (ref "U11") (pin "11") (pinfunction "OUT6_11") (pintype "output"))
    )
    (net (code "216") (name "Net-(U11-OUT7)") (class "Default")
      (node (ref "SV11") (pin "15") (pinfunction "15_15") (pintype "passive"))
      (node (ref "U11") (pin "12") (pinfunction "OUT7_12") (pintype "output"))
    )
    (net (code "217") (name "Net-(U11-OUT8)") (class "Default")
      (node (ref "SV11") (pin "2") (pinfunction "2_2") (pintype "passive"))
      (node (ref "U11") (pin "13") (pinfunction "OUT8_13") (pintype "output"))
    )
    (net (code "218") (name "Net-(U11-OUT9)") (class "Default")
      (node (ref "SV11") (pin "4") (pinfunction "4_4") (pintype "passive"))
      (node (ref "U11") (pin "14") (pinfunction "OUT9_14") (pintype "output"))
    )
    (net (code "219") (name "Net-(U11-OUT10)") (class "Default")
      (node (ref "SV11") (pin "6") (pinfunction "6_6") (pintype "passive"))
      (node (ref "U11") (pin "15") (pinfunction "OUT10_15") (pintype "output"))
    )
    (net (code "220") (name "Net-(U11-OUT11)") (class "Default")
      (node (ref "SV11") (pin "8") (pinfunction "8_8") (pintype "passive"))
      (node (ref "U11") (pin "16") (pinfunction "OUT11_16") (pintype "output"))
    )
    (net (code "221") (name "Net-(U11-OUT12)") (class "Default")
      (node (ref "SV11") (pin "10") (pinfunction "10_10") (pintype "passive"))
      (node (ref "U11") (pin "17") (pinfunction "OUT12_17") (pintype "output"))
    )
    (net (code "222") (name "Net-(U11-OUT13)") (class "Default")
      (node (ref "SV11") (pin "12") (pinfunction "12_12") (pintype "passive"))
      (node (ref "U11") (pin "18") (pinfunction "OUT13_18") (pintype "output"))
    )
    (net (code "223") (name "Net-(U11-OUT14)") (class "Default")
      (node (ref "SV11") (pin "14") (pinfunction "14_14") (pintype "passive"))
      (node (ref "U11") (pin "19") (pinfunction "OUT14_19") (pintype "output"))
    )
    (net (code "224") (name "Net-(U11-OUT15)") (class "Default")
      (node (ref "SV11") (pin "16") (pinfunction "16_16") (pintype "passive"))
      (node (ref "U11") (pin "20") (pinfunction "OUT15_20") (pintype "output"))
    )
    (net (code "225") (name "Net-(U11-R-EXT)") (class "Default")
      (node (ref "R12") (pin "2") (pinfunction "2_2") (pintype "passive"))
      (node (ref "U11") (pin "23") (pinfunction "R-EXT_23") (pintype "input"))
    )
    (net (code "226") (name "Net-(U11-SDO)") (class "Default")
      (node (ref "U11") (pin "22") (pinfunction "SDO_22") (pintype "output"))
      (node (ref "U12") (pin "2") (pinfunction "SDI_2") (pintype "input"))
    )
    (net (code "227") (name "Net-(U12-OUT0)") (class "Default")
      (node (ref "SV12") (pin "1") (pinfunction "1_1") (pintype "passive"))
      (node (ref "U12") (pin "5") (pinfunction "OUT0_5") (pintype "output"))
    )
    (net (code "228") (name "Net-(U12-OUT1)") (class "Default")
      (node (ref "SV12") (pin "3") (pinfunction "3_3") (pintype "passive"))
      (node (ref "U12") (pin "6") (pinfunction "OUT1_6") (pintype "output"))
    )
    (net (code "229") (name "Net-(U12-OUT2)") (class "Default")
      (node (ref "SV12") (pin "5") (pinfunction "5_5") (pintype "passive"))
      (node (ref "U12") (pin "7") (pinfunction "OUT2_7") (pintype "output"))
    )
    (net (code "230") (name "Net-(U12-OUT3)") (class "Default")
      (node (ref "SV12") (pin "7") (pinfunction "7_7") (pintype "passive"))
      (node (ref "U12") (pin "8") (pinfunction "OUT3_8") (pintype "output"))
    )
    (net (code "231") (name "Net-(U12-OUT4)") (class "Default")
      (node (ref "SV12") (pin "9") (pinfunction "9_9") (pintype "passive"))
      (node (ref "U12") (pin "9") (pinfunction "OUT4_9") (pintype "output"))
    )
    (net (code "232") (name "Net-(U12-OUT5)") (class "Default")
      (node (ref "SV12") (pin "11") (pinfunction "11_11") (pintype "passive"))
      (node (ref "U12") (pin "10") (pinfunction "OUT5_10") (pintype "output"))
    )
    (net (code "233") (name "Net-(U12-OUT6)") (class "Default")
      (node (ref "SV12") (pin "13") (pinfunction "13_13") (pintype "passive"))
      (node (ref "U12") (pin "11") (pinfunction "OUT6_11") (pintype "output"))
    )
    (net (code "234") (name "Net-(U12-OUT7)") (class "Default")
      (node (ref "SV12") (pin "15") (pinfunction "15_15") (pintype "passive"))
      (node (ref "U12") (pin "12") (pinfunction "OUT7_12") (pintype "output"))
    )
    (net (code "235") (name "Net-(U12-OUT8)") (class "Default")
      (node (ref "SV12") (pin "2") (pinfunction "2_2") (pintype "passive"))
      (node (ref "U12") (pin "13") (pinfunction "OUT8_13") (pintype "output"))
    )
    (net (code "236") (name "Net-(U12-OUT9)") (class "Default")
      (node (ref "SV12") (pin "4") (pinfunction "4_4") (pintype "passive"))
      (node (ref "U12") (pin "14") (pinfunction "OUT9_14") (pintype "output"))
    )
    (net (code "237") (name "Net-(U12-OUT10)") (class "Default")
      (node (ref "SV12") (pin "6") (pinfunction "6_6") (pintype "passive"))
      (node (ref "U12") (pin "15") (pinfunction "OUT10_15") (pintype "output"))
    )
    (net (code "238") (name "Net-(U12-OUT11)") (class "Default")
      (node (ref "SV12") (pin "8") (pinfunction "8_8") (pintype "passive"))
      (node (ref "U12") (pin "16") (pinfunction "OUT11_16") (pintype "output"))
    )
    (net (code "239") (name "Net-(U12-OUT12)") (class "Default")
      (node (ref "SV12") (pin "10") (pinfunction "10_10") (pintype "passive"))
      (node (ref "U12") (pin "17") (pinfunction "OUT12_17") (pintype "output"))
    )
    (net (code "240") (name "Net-(U12-OUT13)") (class "Default")
      (node (ref "SV12") (pin "12") (pinfunction "12_12") (pintype "passive"))
      (node (ref "U12") (pin "18") (pinfunction "OUT13_18") (pintype "output"))
    )
    (net (code "241") (name "Net-(U12-OUT14)") (class "Default")
      (node (ref "SV12") (pin "14") (pinfunction "14_14") (pintype "passive"))
      (node (ref "U12") (pin "19") (pinfunction "OUT14_19") (pintype "output"))
    )
    (net (code "242") (name "Net-(U12-OUT15)") (class "Default")
      (node (ref "SV12") (pin "16") (pinfunction "16_16") (pintype "passive"))
      (node (ref "U12") (pin "20") (pinfunction "OUT15_20") (pintype "output"))
    )
    (net (code "243") (name "Net-(U12-R-EXT)") (class "Default")
      (node (ref "R13") (pin "2") (pinfunction "2_2") (pintype "passive"))
      (node (ref "U12") (pin "23") (pinfunction "R-EXT_23") (pintype "input"))
    )
    (net (code "244") (name "SDI_B") (class "Default")
      (node (ref "SV13") (pin "12") (pinfunction "12_12") (pintype "passive"))
      (node (ref "U9") (pin "2") (pinfunction "SDI_2") (pintype "input"))
    )
    (net (code "245") (name "SDI_G") (class "Default")
      (node (ref "SV13") (pin "10") (pinfunction "10_10") (pintype "passive"))
      (node (ref "U5") (pin "2") (pinfunction "SDI_2") (pintype "input"))
    )
    (net (code "246") (name "SDI_R") (class "Default")
      (node (ref "SV13") (pin "8") (pinfunction "8_8") (pintype "passive"))
      (node (ref "U1") (pin "2") (pinfunction "SDI_2") (pintype "input"))
    )
    (net (code "247") (name "unconnected-(SV13-Pad14)") (class "Default")
      (node (ref "SV13") (pin "14") (pinfunction "14_14") (pintype "passive"))
    )
    (net (code "248") (name "unconnected-(SV13-Pad16)") (class "Default")
      (node (ref "SV13") (pin "16") (pinfunction "16_16") (pintype "passive"))
    )
    (net (code "249") (name "unconnected-(SV14-Pad2)") (class "Default")
      (node (ref "SV14") (pin "2") (pinfunction "2_2") (pintype "passive"))
    )
    (net (code "250") (name "unconnected-(SV14-Pad4)") (class "Default")
      (node (ref "SV14") (pin "4") (pinfunction "4_4") (pintype "passive"))
    )
    (net (code "251") (name "unconnected-(SV14-Pad6)") (class "Default")
      (node (ref "SV14") (pin "6") (pinfunction "6_6") (pintype "passive"))
    )
    (net (code "252") (name "unconnected-(SV14-Pad8)") (class "Default")
      (node (ref "SV14") (pin "8") (pinfunction "8_8") (pintype "passive"))
    )
    (net (code "253") (name "unconnected-(SV14-Pad10)") (class "Default")
      (node (ref "SV14") (pin "10") (pinfunction "10_10") (pintype "passive"))
    )
    (net (code "254") (name "unconnected-(SV14-Pad12)") (class "Default")
      (node (ref "SV14") (pin "12") (pinfunction "12_12") (pintype "passive"))
    )
    (net (code "255") (name "unconnected-(SV14-Pad14)") (class "Default")
      (node (ref "SV14") (pin "14") (pinfunction "14_14") (pintype "passive"))
    )
    (net (code "256") (name "unconnected-(SV14-Pad16)") (class "Default")
      (node (ref "SV14") (pin "16") (pinfunction "16_16") (pintype "passive"))
    )
    (net (code "257") (name "unconnected-(U4-SDO-Pad22)") (class "Default")
      (node (ref "U4") (pin "22") (pinfunction "SDO_22") (pintype "output"))
    )
    (net (code "258") (name "unconnected-(U8-SDO-Pad22)") (class "Default")
      (node (ref "U8") (pin "22") (pinfunction "SDO_22") (pintype "output"))
    )
    (net (code "259") (name "unconnected-(U12-SDO-Pad22)") (class "Default")
      (node (ref "U12") (pin "22") (pinfunction "SDO_22") (pintype "output"))
    )
  )
)
